# Alpha_Power_Board_v7.net
KiCad netlist of a schematic drawn in EAGLE
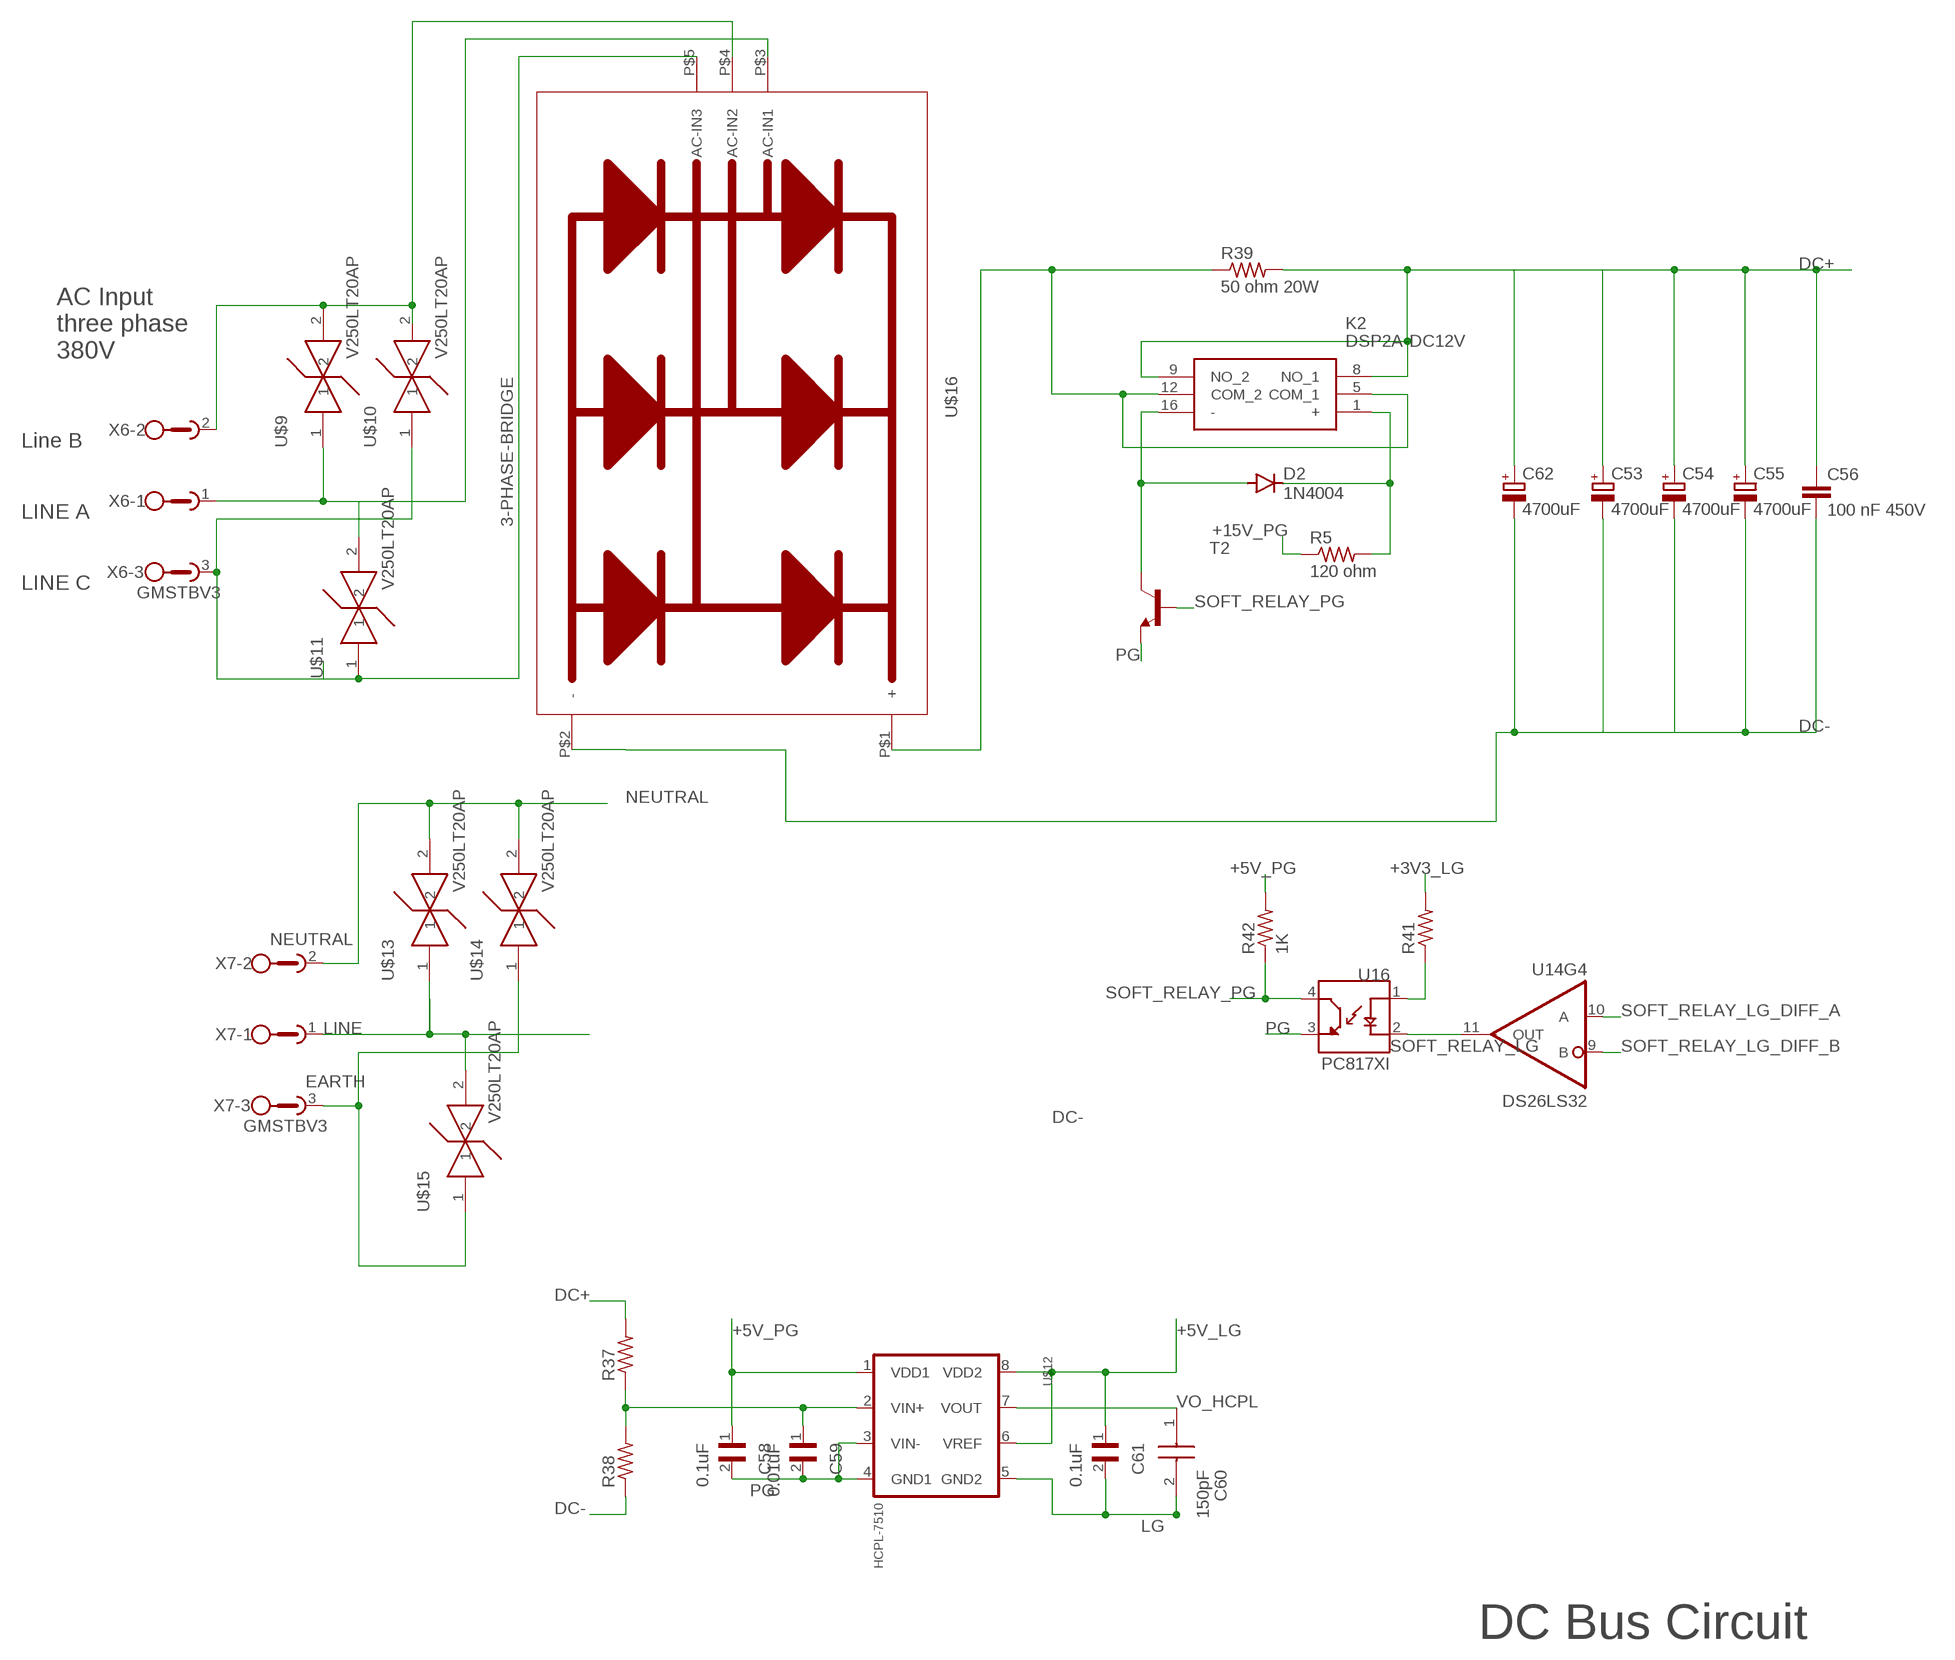
[diagram p0: schematic, sheet 1]
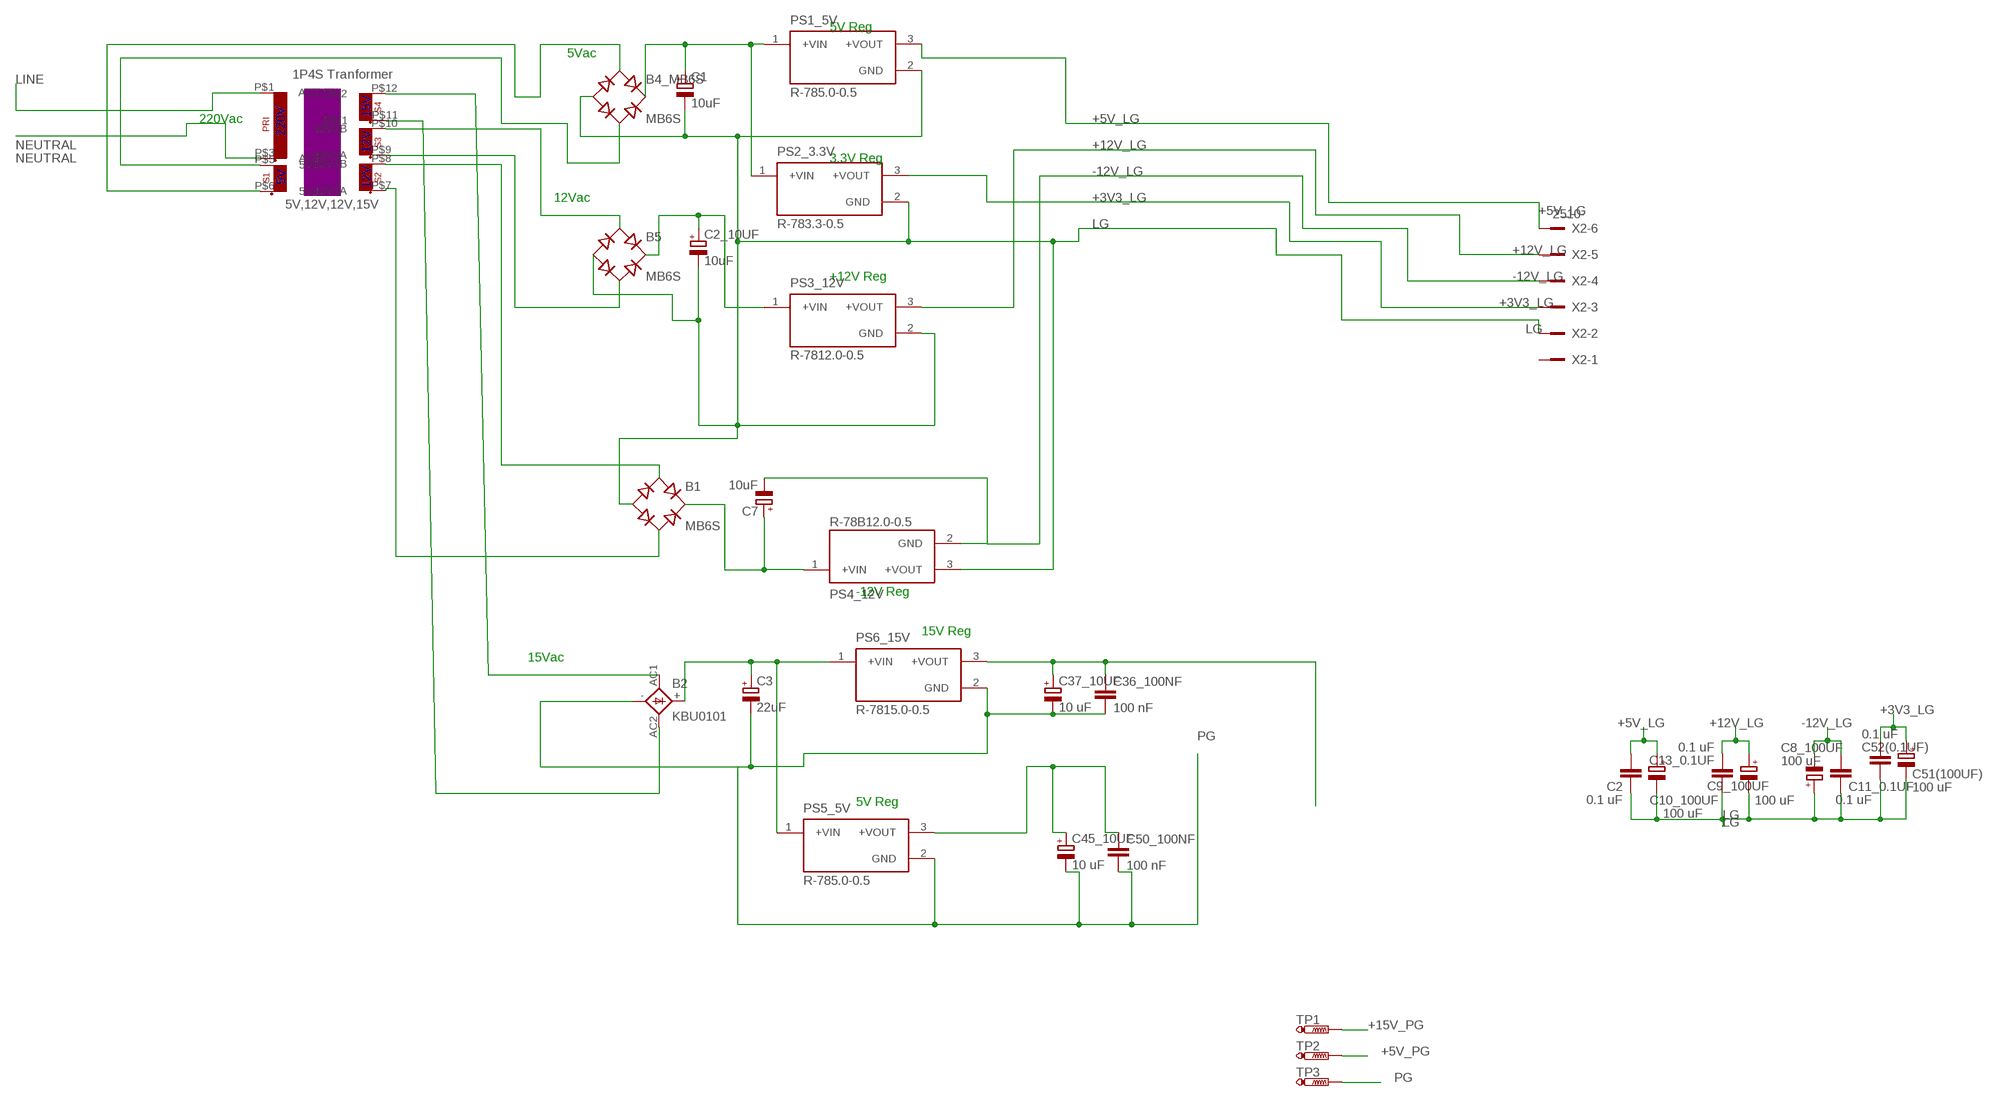
[diagram p1: schematic, sheet 2]
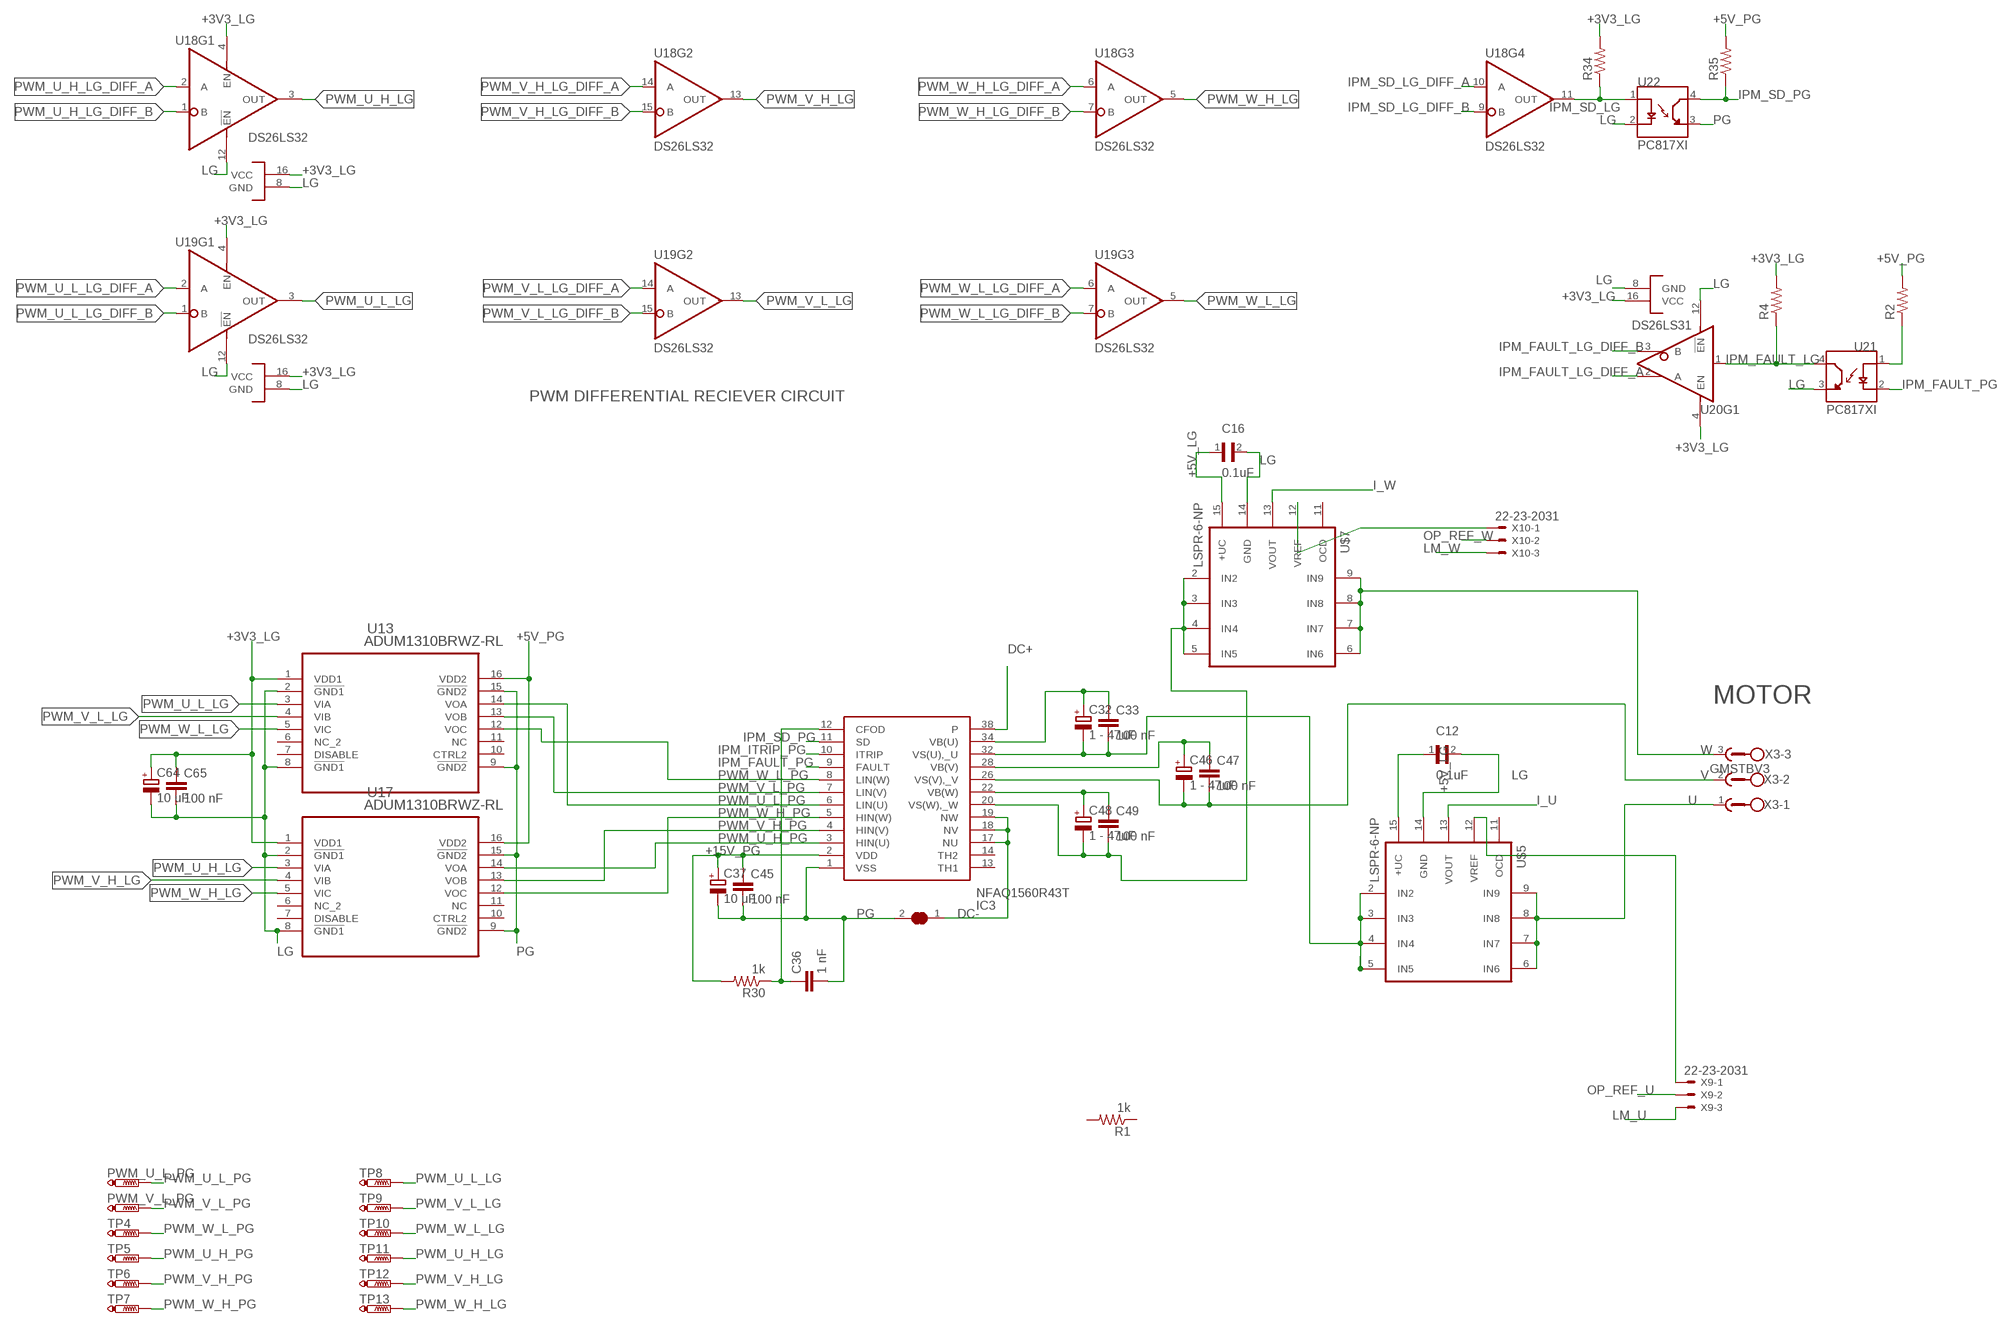
[diagram p2: schematic, sheet 3]
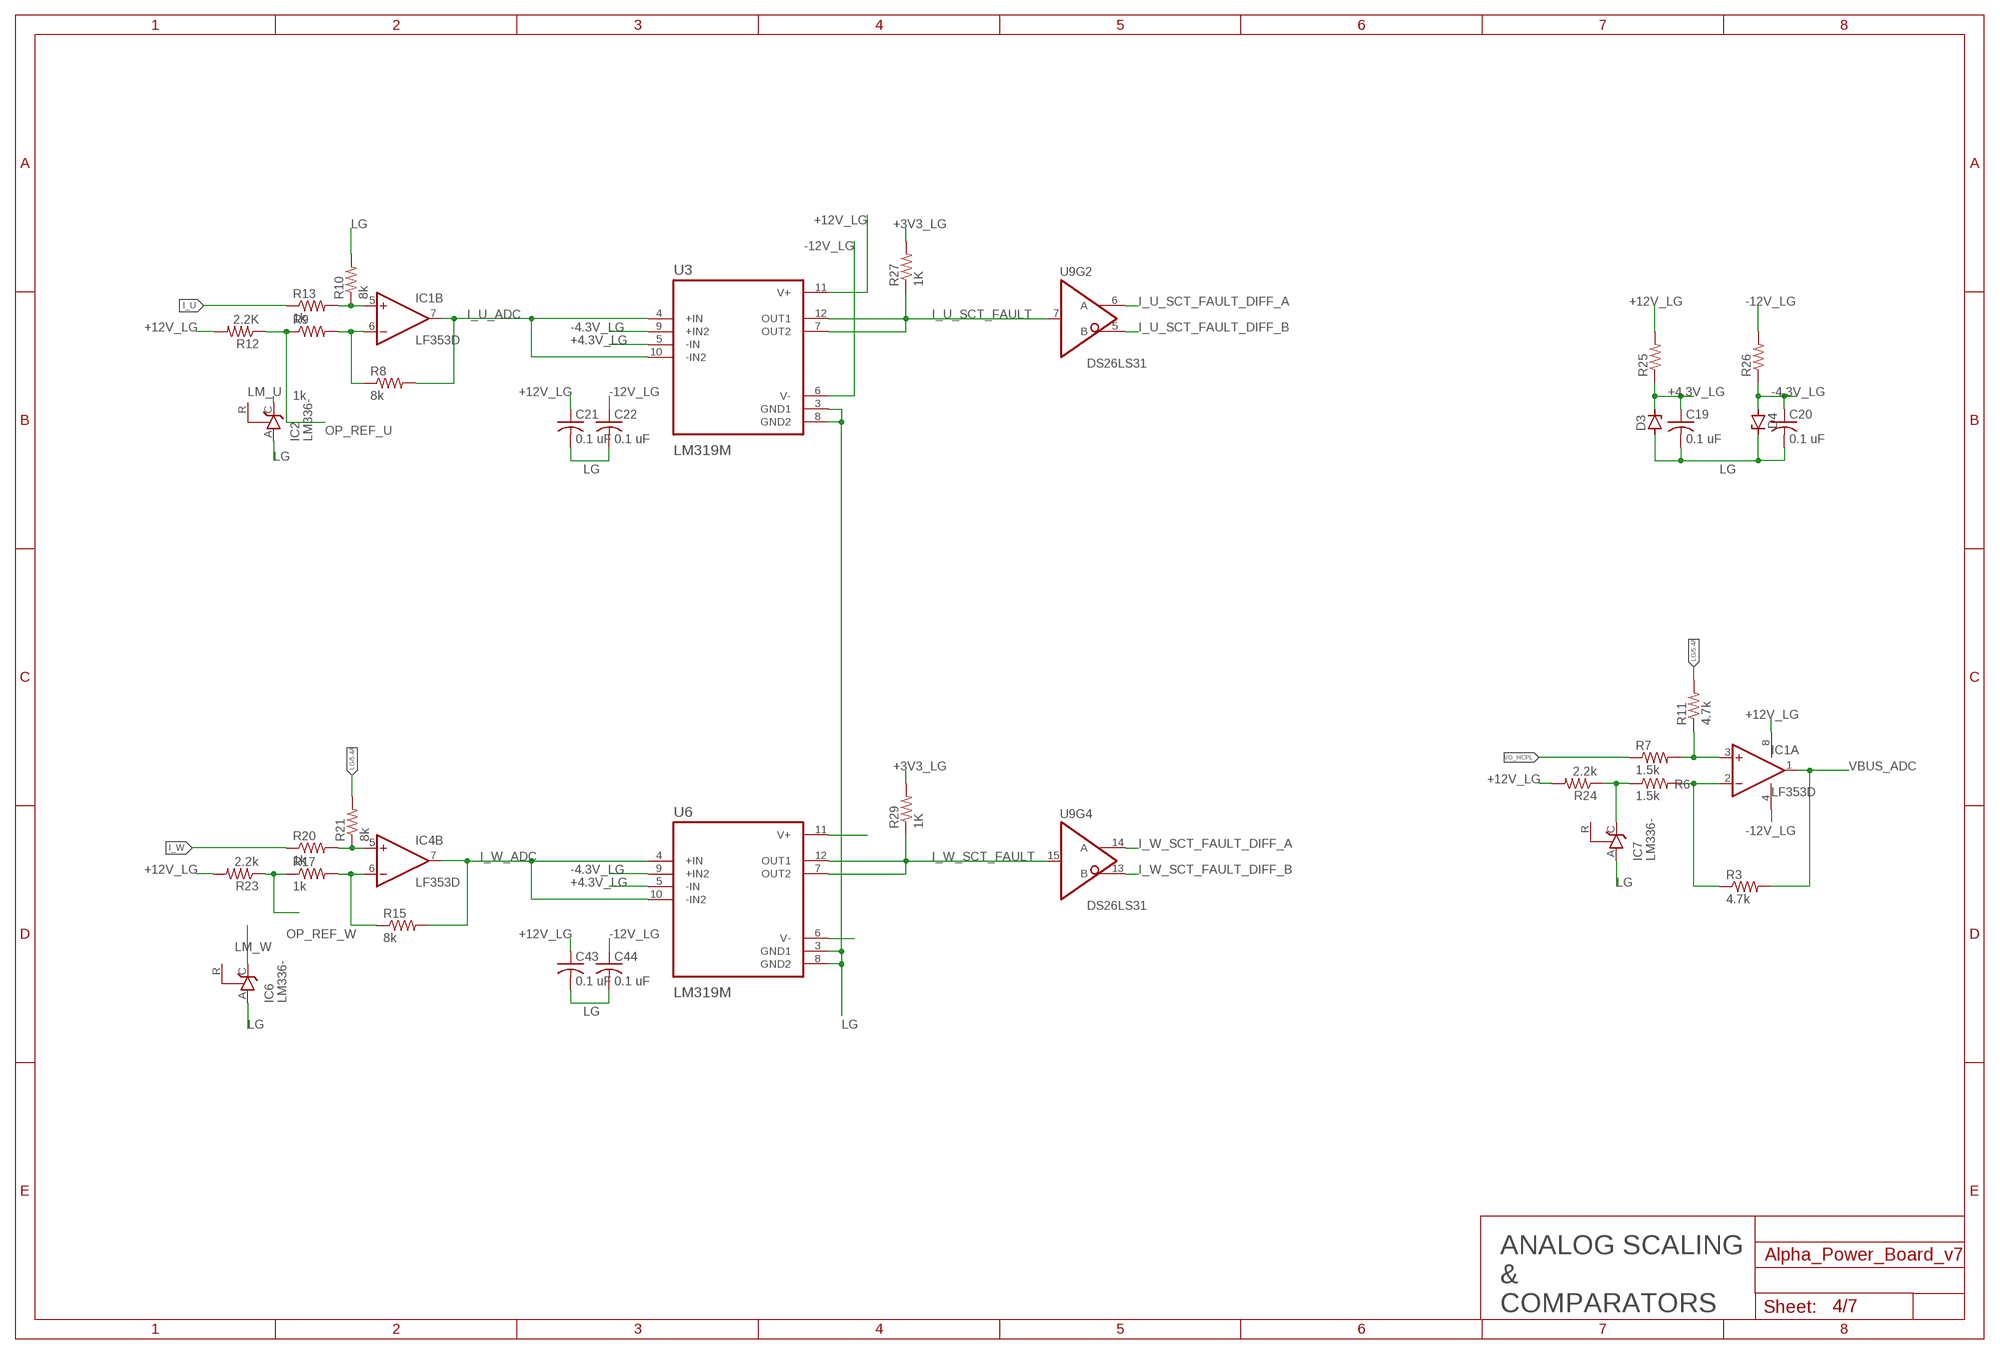
[diagram p3: schematic, sheet 4]
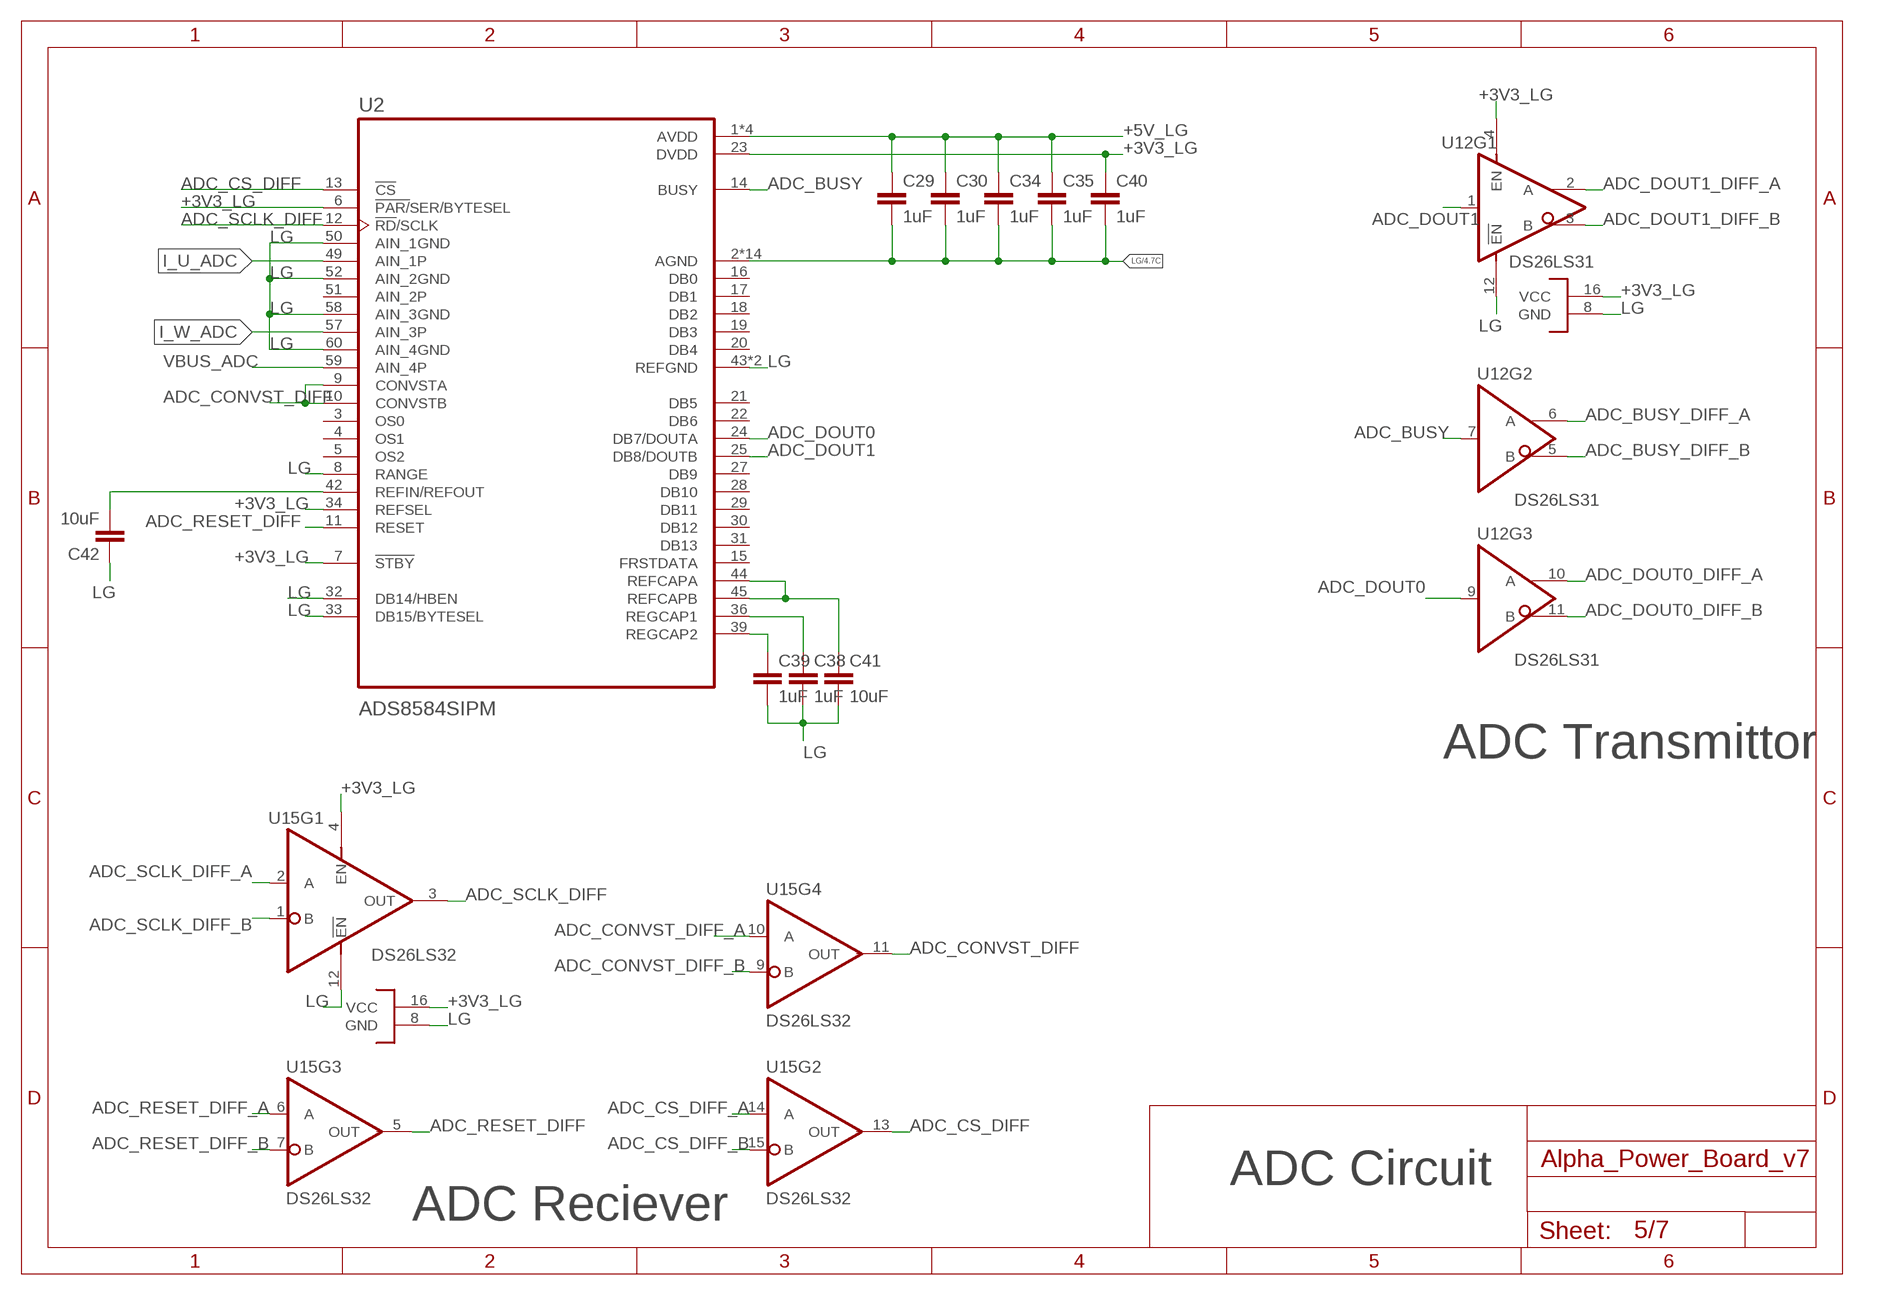
[diagram p4: schematic, sheet 5]
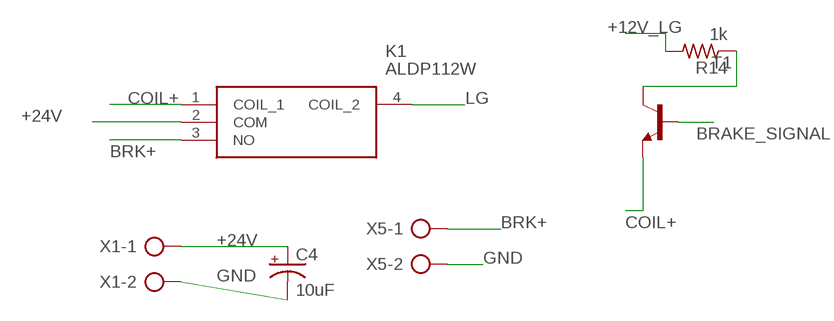
[diagram p5: schematic, sheet 6]
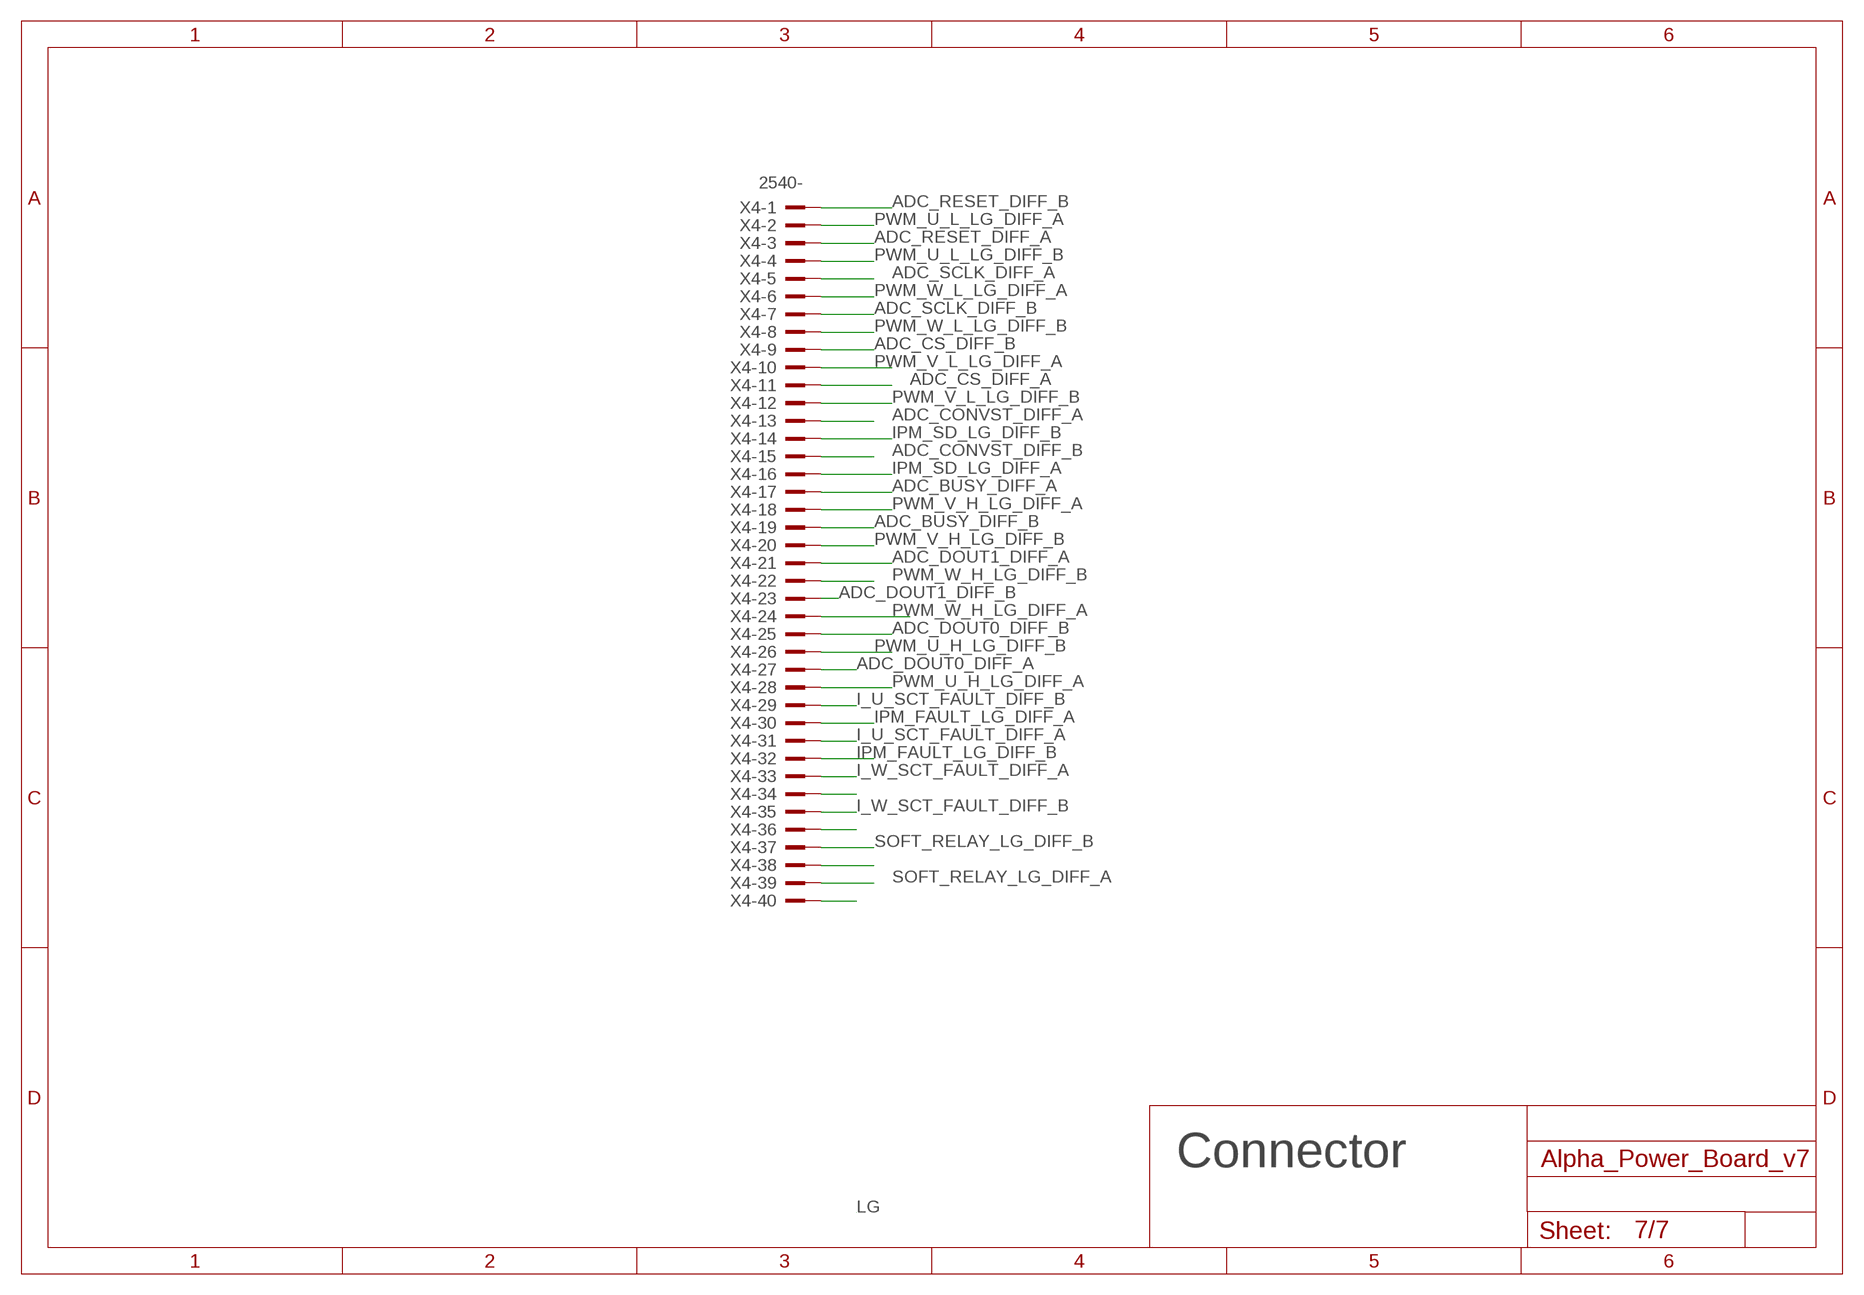
[diagram p6: schematic, sheet 7]

(export (version "E")
  (design (tool "Eeschema 10.0.6"))
  (components
    (comp (ref "B1")
      (value "MB6S")
      (footprint "eagle-import:SOIC-4")
      (libsource (lib "eagle-import") (part "MBS6"))
    )
    (comp (ref "B2")
      (value "KBU0101")
      (footprint "eagle-import:KBU")
      (libsource (lib "eagle-import") (part "KBU"))
    )
    (comp (ref "B4_MB6S")
      (value "MB6S")
      (footprint "eagle-import:SOIC-4")
      (libsource (lib "eagle-import") (part "MBS6"))
    )
    (comp (ref "B5")
      (value "MB6S")
      (footprint "eagle-import:SOIC-4")
      (libsource (lib "eagle-import") (part "MBS6"))
    )
    (comp (ref "C1")
      (value "10uF")
      (footprint "eagle-import:E2,5-6E")
      (libsource (lib "eagle-import") (part "rcl_334_CPOL-EUE2,5-6E"))
    )
    (comp (ref "C2")
      (value "0.1 uF")
      (footprint "eagle-import:C1206")
      (libsource (lib "eagle-import") (part "C-EUC1206"))
    )
    (comp (ref "C2_10UF")
      (value "10uF")
      (footprint "eagle-import:E2,5-6E")
      (libsource (lib "eagle-import") (part "rcl_334_CPOL-EUE2,5-6E"))
    )
    (comp (ref "C3")
      (value "22uF")
      (footprint "eagle-import:E2,5-6E")
      (libsource (lib "eagle-import") (part "rcl_334_CPOL-EUE2,5-6E"))
    )
    (comp (ref "C7")
      (value "10uF")
      (footprint "eagle-import:E2,5-6E")
      (libsource (lib "eagle-import") (part "rcl_334_CPOL-EUE2,5-6E"))
    )
    (comp (ref "C8_100UF")
      (value "100 uF")
      (footprint "eagle-import:153CLV-0605")
      (libsource (lib "eagle-import") (part "CPOL-EU153CLV-0605"))
    )
    (comp (ref "C9_100UF")
      (value "100 uF")
      (footprint "eagle-import:153CLV-0605")
      (libsource (lib "eagle-import") (part "CPOL-EU153CLV-0605"))
    )
    (comp (ref "C10_100UF")
      (value "100 uF")
      (footprint "eagle-import:153CLV-0605")
      (libsource (lib "eagle-import") (part "CPOL-EU153CLV-0605"))
    )
    (comp (ref "C11_0.1UF")
      (value "0.1 uF")
      (footprint "eagle-import:C1206")
      (libsource (lib "eagle-import") (part "rcl_334_C-EUC1206"))
    )
    (comp (ref "C13_0.1UF")
      (value "0.1 uF")
      (footprint "eagle-import:C1206")
      (libsource (lib "eagle-import") (part "C-EUC1206"))
    )
    (comp (ref "C36_100NF")
      (value "100 nF")
      (footprint "eagle-import:C025-025X050")
      (libsource (lib "eagle-import") (part "C-EU025-025X050"))
    )
    (comp (ref "C37_10UF")
      (value "10 uF")
      (footprint "eagle-import:TT2D5")
      (libsource (lib "eagle-import") (part "CPOL-EUTT2D5"))
    )
    (comp (ref "C45_10UF")
      (value "10 uF")
      (footprint "eagle-import:TT2D5")
      (libsource (lib "eagle-import") (part "CPOL-EUTT2D5"))
    )
    (comp (ref "C50_100NF")
      (value "100 nF")
      (footprint "eagle-import:C025-025X050")
      (libsource (lib "eagle-import") (part "C-EU025-025X050"))
    )
    (comp (ref "C51(100UF)")
      (value "100 uF")
      (footprint "eagle-import:153CLV-0605")
      (libsource (lib "eagle-import") (part "CPOL-EU153CLV-0605"))
    )
    (comp (ref "C52(0.1UF)")
      (value "0.1 uF")
      (footprint "eagle-import:C1206")
      (libsource (lib "eagle-import") (part "C-EUC1206"))
    )
    (comp (ref "PS1_5V")
      (value "R-785.0-0.5")
      (footprint "eagle-import:CONV_R-78E5.0-0.5")
      (fields (field (name "MF") "Recom Power") (field (name "MP") "R-78E5.0-0.5"))
      (libsource (lib "eagle-import") (part "R-78E5.0-0.5"))
    )
    (comp (ref "PS2_3.3V")
      (value "R-783.3-0.5")
      (footprint "eagle-import:CONV_R-78E5.0-0.5")
      (fields (field (name "MF") "Recom Power") (field (name "MP") "R-78E5.0-0.5"))
      (libsource (lib "eagle-import") (part "R-78E5.0-0.5"))
    )
    (comp (ref "PS3_12V")
      (value "R-7812.0-0.5")
      (footprint "eagle-import:CONV_R-78E5.0-0.5")
      (fields (field (name "MF") "Recom Power") (field (name "MP") "R-78E5.0-0.5"))
      (libsource (lib "eagle-import") (part "R-78E5.0-0.5"))
    )
    (comp (ref "PS4_12V")
      (value "R-78B12.0-0.5")
      (footprint "eagle-import:CONV_R-78E5.0-0.5")
      (fields (field (name "MF") "Recom Power") (field (name "MP") "R-78E5.0-0.5"))
      (libsource (lib "eagle-import") (part "R-78E5.0-0.5"))
    )
    (comp (ref "PS5_5V")
      (value "R-785.0-0.5")
      (footprint "eagle-import:CONV_R-78E5.0-0.5")
      (fields (field (name "MF") "Recom Power") (field (name "MP") "R-78E5.0-0.5"))
      (libsource (lib "eagle-import") (part "R-78E5.0-0.5"))
    )
    (comp (ref "PS6_15V")
      (value "R-7815.0-0.5")
      (footprint "eagle-import:CONV_R-78E5.0-0.5")
      (fields (field (name "MF") "Recom Power") (field (name "MP") "R-78E5.0-0.5"))
      (libsource (lib "eagle-import") (part "R-78E5.0-0.5"))
    )
    (comp (ref "TP1")
      (value "PTR1PAD1-13")
      (footprint "eagle-import:P1-13")
      (libsource (lib "eagle-import") (part "PTR1PAD1-13"))
    )
    (comp (ref "TP2")
      (value "PTR1PAD1-13")
      (footprint "eagle-import:P1-13")
      (libsource (lib "eagle-import") (part "PTR1PAD1-13"))
    )
    (comp (ref "TP3")
      (value "PTR1PAD1-13")
      (footprint "eagle-import:P1-13")
      (libsource (lib "eagle-import") (part "PTR1PAD1-13"))
    )
    (comp (ref "U$1")
      (value "TRANSFORMERTHROUGH-HOLE")
      (footprint "eagle-import:T1P2S")
      (libsource (lib "eagle-import") (part "TRANSFORMERTHROUGH-HOLE"))
    )
    (comp (ref "X2")
      (value "2510-")
      (footprint "eagle-import:PAK100_2500-10")
      (fields (field (name "MF") "3M") (field (name "MPN") "2510-6002UB"))
      (libsource (lib "eagle-import") (part "2510-"))
    )
    (comp (ref "C53")
      (value "4700uF")
      (footprint "eagle-import:EB35D")
      (libsource (lib "eagle-import") (part "resistor_CPOL-EUE10-35"))
    )
    (comp (ref "C54")
      (value "4700uF")
      (footprint "eagle-import:EB35D")
      (libsource (lib "eagle-import") (part "resistor_CPOL-EUE10-35"))
    )
    (comp (ref "C55")
      (value "4700uF")
      (footprint "eagle-import:EB35D")
      (libsource (lib "eagle-import") (part "resistor_CPOL-EUE10-35"))
    )
    (comp (ref "C56")
      (value "100 nF 450V")
      (footprint "eagle-import:C102-064X133")
      (libsource (lib "eagle-import") (part "C-EU102-064X133"))
    )
    (comp (ref "C58")
      (value "0.1uF")
      (footprint "eagle-import:CAPC3316X140N")
      (fields (field (name "MF") "KEMET") (field (name "MP") "C1206X104J3REC7210"))
      (libsource (lib "eagle-import") (part "C1206X104J3REC7210"))
    )
    (comp (ref "C59")
      (value "0.01uF")
      (footprint "eagle-import:CAPC3316X140N")
      (fields (field (name "MF") "KEMET") (field (name "MP") "C1206X104J3REC7210"))
      (libsource (lib "eagle-import") (part "C1206X104J3REC7210"))
    )
    (comp (ref "C60")
      (value "150pF")
      (footprint "eagle-import:CAP150PF")
      (fields
        (field (name "MANUFACTURER_PART_NUMBER") "GCM31A7U2J151JX01D")
        (field (name "MOUSER_PART_NUMBER") "81-GCM31A7U2J151JX1D")
      )
      (libsource (lib "eagle-import") (part "CAP150PF"))
    )
    (comp (ref "C61")
      (value "0.1uF")
      (footprint "eagle-import:CAPC3316X140N")
      (fields (field (name "MF") "KEMET") (field (name "MP") "C1206X104J3REC7210"))
      (libsource (lib "eagle-import") (part "C1206X104J3REC7210"))
    )
    (comp (ref "C62")
      (value "4700uF")
      (footprint "eagle-import:EB35D")
      (libsource (lib "eagle-import") (part "resistor_CPOL-EUE10-35"))
    )
    (comp (ref "D2")
      (value "1N4004")
      (footprint "eagle-import:DO41-10")
      (libsource (lib "eagle-import") (part "1N4004"))
    )
    (comp (ref "K2")
      (value "DSP2A-DC12V")
      (footprint "eagle-import:DSP2ADC12V")
      (fields (field (name "MOUSER_PART_NUMBER") "769-DSP2A-DC12V"))
      (libsource (lib "eagle-import") (part "DSP2A-DC12V"))
    )
    (comp (ref "R5")
      (value "120 ohm")
      (footprint "eagle-import:0207_15")
      (libsource (lib "eagle-import") (part "rcl_334_R-US_0207/15"))
    )
    (comp (ref "R37")
      (value "R-US_0309/12")
      (footprint "eagle-import:0309_12")
      (libsource (lib "eagle-import") (part "rcl_334_R-US_0309/12"))
    )
    (comp (ref "R38")
      (value "R-US_0309/12")
      (footprint "eagle-import:0309_12")
      (libsource (lib "eagle-import") (part "rcl_334_R-US_0309/12"))
    )
    (comp (ref "R39")
      (value "50 ohm 20W")
      (footprint "eagle-import:B20J50RE")
      (libsource (lib "eagle-import") (part "B20J50RE"))
    )
    (comp (ref "R41")
      (value "R-US_R1206")
      (footprint "eagle-import:R1206")
      (libsource (lib "eagle-import") (part "rcl@2_R-US_R1206"))
    )
    (comp (ref "R42")
      (value "1K")
      (footprint "eagle-import:R1206")
      (libsource (lib "eagle-import") (part "rcl@2_R-US_R1206"))
    )
    (comp (ref "T2")
      (value "MMBT2222ALT1-NPN-SOT23-BEC")
      (footprint "eagle-import:SOT23-BEC")
      (libsource (lib "eagle-import") (part "-NPN-SOT23-BECMMBT2222ALT1"))
    )
    (comp (ref "U$9")
      (value "V250LT20AP")
      (footprint "eagle-import:V250LT20AP")
      (fields (field (name "MF") "Littelfuse Inc.") (field (name "MP") "V18ZA2P"))
      (libsource (lib "eagle-import") (part "V250LT20AP"))
    )
    (comp (ref "U$10")
      (value "V250LT20AP")
      (footprint "eagle-import:V250LT20AP")
      (fields (field (name "MF") "Littelfuse Inc.") (field (name "MP") "V18ZA2P"))
      (libsource (lib "eagle-import") (part "V250LT20AP"))
    )
    (comp (ref "U$11")
      (value "V250LT20AP")
      (footprint "eagle-import:V250LT20AP")
      (fields (field (name "MF") "Littelfuse Inc.") (field (name "MP") "V18ZA2P"))
      (libsource (lib "eagle-import") (part "V250LT20AP"))
    )
    (comp (ref "U$12")
      (value "HCPL-7510")
      (footprint "eagle-import:HCPL-7510")
      (libsource (lib "eagle-import") (part "HCPL-7510U"))
    )
    (comp (ref "U$13")
      (value "V250LT20AP")
      (footprint "eagle-import:V250LT20AP")
      (fields (field (name "MF") "Littelfuse Inc.") (field (name "MP") "V18ZA2P"))
      (libsource (lib "eagle-import") (part "V250LT20AP"))
    )
    (comp (ref "U$14")
      (value "V250LT20AP")
      (footprint "eagle-import:V250LT20AP")
      (fields (field (name "MF") "Littelfuse Inc.") (field (name "MP") "V18ZA2P"))
      (libsource (lib "eagle-import") (part "V250LT20AP"))
    )
    (comp (ref "U$15")
      (value "V250LT20AP")
      (footprint "eagle-import:V250LT20AP")
      (fields (field (name "MF") "Littelfuse Inc.") (field (name "MP") "V18ZA2P"))
      (libsource (lib "eagle-import") (part "V250LT20AP"))
    )
    (comp (ref "U$16")
      (value "3-PHASE-BRIDGE")
      (footprint "eagle-import:3-PHASE-BRIDGE")
      (libsource (lib "eagle-import") (part "3-PHASE-BRIDGE"))
    )
    (comp (ref "U14")
      (value "DS26LS32")
      (footprint "eagle-import:SOIC_16")
      (libsource (lib "eagle-import") (part "DS26LS32"))
    )
    (comp (ref "U16")
      (value "PC817XI")
      (footprint "eagle-import:SOIC254P975X460-4N")
      (fields (field (name "MF") "Sharp Microelectronics"))
      (libsource (lib "eagle-import") (part "PC817XI"))
    )
    (comp (ref "X6")
      (value "GMSTBV3")
      (footprint "eagle-import:GMSTBV3")
      (fields (field (name "MPN") "GMSTBVA2,5/3-G-7,62"))
      (libsource (lib "eagle-import") (part "con-phoenix-762_177_GMSTBV3"))
    )
    (comp (ref "X7")
      (value "GMSTBV3")
      (footprint "eagle-import:GMSTBV3")
      (fields (field (name "MPN") "GMSTBVA2,5/3-G-7,62"))
      (libsource (lib "eagle-import") (part "GMSTBV3"))
    )
    (comp (ref "C4")
      (value "10uF")
      (footprint "eagle-import:E2,5-6E")
      (libsource (lib "eagle-import") (part "CPOL-USE2,5-6E"))
    )
    (comp (ref "K1")
      (value "ALDP112W")
      (footprint "eagle-import:ALDP112W")
      (fields (field (name "MOUSER_PART_NUMBER") "769-ALDP112W"))
      (libsource (lib "eagle-import") (part "ALDP112W"))
    )
    (comp (ref "R14")
      (value "1k")
      (footprint "eagle-import:0204V")
      (libsource (lib "eagle-import") (part "rcl_R-US_0204/2V"))
    )
    (comp (ref "T1")
      (value "MMBT2222ALT1-NPN-SOT23-BEC")
      (footprint "eagle-import:SOT23-BEC")
      (libsource (lib "eagle-import") (part "-NPN-SOT23-BECMMBT2222ALT1"))
    )
    (comp (ref "X1")
      (value "AK500/2-H")
      (footprint "eagle-import:AK500_2-H")
      (libsource (lib "eagle-import") (part "AK500/2-H"))
    )
    (comp (ref "X5")
      (value "AK500/2-H")
      (footprint "eagle-import:AK500_2-H")
      (libsource (lib "eagle-import") (part "AK500/2-H"))
    )
    (comp (ref "C29")
      (value "1uF")
      (footprint "eagle-import:C0603")
      (libsource (lib "eagle-import") (part "rcl@1_C-EUC0603"))
    )
    (comp (ref "C30")
      (value "1uF")
      (footprint "eagle-import:C0603")
      (libsource (lib "eagle-import") (part "rcl@1_C-EUC0603"))
    )
    (comp (ref "C34")
      (value "1uF")
      (footprint "eagle-import:C0603")
      (libsource (lib "eagle-import") (part "rcl@1_C-EUC0603"))
    )
    (comp (ref "C35")
      (value "1uF")
      (footprint "eagle-import:C0603")
      (libsource (lib "eagle-import") (part "rcl@1_C-EUC0603"))
    )
    (comp (ref "C38")
      (value "1uF")
      (footprint "eagle-import:C0603")
      (libsource (lib "eagle-import") (part "rcl@1_C-EUC0603"))
    )
    (comp (ref "C39")
      (value "1uF")
      (footprint "eagle-import:C0603")
      (libsource (lib "eagle-import") (part "rcl@1_C-EUC0603"))
    )
    (comp (ref "C40")
      (value "1uF")
      (footprint "eagle-import:C0603")
      (libsource (lib "eagle-import") (part "rcl@1_C-EUC0603"))
    )
    (comp (ref "C41")
      (value "10uF")
      (footprint "eagle-import:C0603")
      (libsource (lib "eagle-import") (part "rcl@1_C-EUC0603"))
    )
    (comp (ref "C42")
      (value "10uF")
      (footprint "eagle-import:C0603")
      (libsource (lib "eagle-import") (part "rcl@1_C-EUC0603"))
    )
    (comp (ref "U2")
      (value "ADS8584SIPM")
      (footprint "eagle-import:QFP50P1200X1200X160-64N")
      (fields (field (name "MF") "Texas Instruments"))
      (libsource (lib "eagle-import") (part "ADS8584SIPM"))
    )
    (comp (ref "U12")
      (value "DS26LS31")
      (footprint "eagle-import:SOIC_16")
      (libsource (lib "eagle-import") (part "DS26LS31"))
    )
    (comp (ref "U15")
      (value "DS26LS32")
      (footprint "eagle-import:SOIC_16")
      (libsource (lib "eagle-import") (part "DS26LS32"))
    )
    (comp (ref "C19")
      (value "0.1 uF")
      (footprint "eagle-import:C1206")
      (libsource (lib "eagle-import") (part "C-USC1206"))
    )
    (comp (ref "C20")
      (value "0.1 uF")
      (footprint "eagle-import:C1206")
      (libsource (lib "eagle-import") (part "C-USC1206"))
    )
    (comp (ref "C21")
      (value "0.1 uF")
      (footprint "eagle-import:C1206")
      (libsource (lib "eagle-import") (part "C-USC1206"))
    )
    (comp (ref "C22")
      (value "0.1 uF")
      (footprint "eagle-import:C1206")
      (libsource (lib "eagle-import") (part "C-USC1206"))
    )
    (comp (ref "C43")
      (value "0.1 uF")
      (footprint "eagle-import:C1206")
      (libsource (lib "eagle-import") (part "C-USC1206"))
    )
    (comp (ref "C44")
      (value "0.1 uF")
      (footprint "eagle-import:C1206")
      (libsource (lib "eagle-import") (part "C-USC1206"))
    )
    (comp (ref "D3")
      (value "ZENER-DIODETO236")
      (footprint "eagle-import:TO236")
      (libsource (lib "eagle-import") (part "ZENER-DIODETO236"))
    )
    (comp (ref "D4")
      (value "ZENER-DIODETO236")
      (footprint "eagle-import:TO236")
      (fields (field (name "SPICEPREFIX") "D"))
      (libsource (lib "eagle-import") (part "ZENER-DIODETO236"))
    )
    (comp (ref "IC1")
      (value "LF353D")
      (footprint "eagle-import:SO08")
      (fields (field (name "MF") "ON Semiconductor") (field (name "MP") "LF353"))
      (libsource (lib "eagle-import") (part "LF353D"))
    )
    (comp (ref "IC2")
      (value "LM336-")
      (footprint "eagle-import:TO92A_VREF")
      (libsource (lib "eagle-import") (part "LM336-"))
    )
    (comp (ref "IC4")
      (value "LF353D")
      (footprint "eagle-import:SO08")
      (fields (field (name "MF") "ON Semiconductor") (field (name "MP") "LF353"))
      (libsource (lib "eagle-import") (part "LF353D"))
    )
    (comp (ref "IC6")
      (value "LM336-")
      (footprint "eagle-import:TO92A_VREF")
      (libsource (lib "eagle-import") (part "LM336-"))
    )
    (comp (ref "IC7")
      (value "LM336-")
      (footprint "eagle-import:TO92A_VREF")
      (libsource (lib "eagle-import") (part "LM336-"))
    )
    (comp (ref "R3")
      (value "4.7k")
      (footprint "eagle-import:M1206")
      (libsource (lib "eagle-import") (part "R-US_M1206"))
    )
    (comp (ref "R6")
      (value "1.5k")
      (footprint "eagle-import:M1206")
      (libsource (lib "eagle-import") (part "R-US_M1206"))
    )
    (comp (ref "R7")
      (value "1.5k")
      (footprint "eagle-import:R1206")
      (libsource (lib "eagle-import") (part "R-US_R1206"))
    )
    (comp (ref "R8")
      (value "8k")
      (footprint "eagle-import:M1206")
      (libsource (lib "eagle-import") (part "R-US_M1206"))
    )
    (comp (ref "R9")
      (value "1k")
      (footprint "eagle-import:M1206")
      (libsource (lib "eagle-import") (part "R-US_M1206"))
    )
    (comp (ref "R10")
      (value "8k")
      (footprint "eagle-import:M1206")
      (libsource (lib "eagle-import") (part "R-US_M1206"))
    )
    (comp (ref "R11")
      (value "4.7k")
      (footprint "eagle-import:M1206")
      (libsource (lib "eagle-import") (part "R-US_M1206"))
    )
    (comp (ref "R12")
      (value "2.2K")
      (footprint "eagle-import:M1206")
      (libsource (lib "eagle-import") (part "R-US_M1206"))
    )
    (comp (ref "R13")
      (value "1k")
      (footprint "eagle-import:M1206")
      (libsource (lib "eagle-import") (part "R-US_M1206"))
    )
    (comp (ref "R15")
      (value "8k")
      (footprint "eagle-import:M1206")
      (libsource (lib "eagle-import") (part "R-US_M1206"))
    )
    (comp (ref "R17")
      (value "1k")
      (footprint "eagle-import:M1206")
      (libsource (lib "eagle-import") (part "R-US_M1206"))
    )
    (comp (ref "R20")
      (value "1k")
      (footprint "eagle-import:M1206")
      (libsource (lib "eagle-import") (part "R-US_M1206"))
    )
    (comp (ref "R21")
      (value "8k")
      (footprint "eagle-import:M1206")
      (libsource (lib "eagle-import") (part "R-US_M1206"))
    )
    (comp (ref "R23")
      (value "2.2k")
      (footprint "eagle-import:M1206")
      (libsource (lib "eagle-import") (part "R-US_M1206"))
    )
    (comp (ref "R24")
      (value "2.2k")
      (footprint "eagle-import:M1206")
      (libsource (lib "eagle-import") (part "R-US_M1206"))
    )
    (comp (ref "R25")
      (value "R-US_M1206")
      (footprint "eagle-import:M1206")
      (libsource (lib "eagle-import") (part "rcl@2_R-US_M1206"))
    )
    (comp (ref "R26")
      (value "R-US_M1206")
      (footprint "eagle-import:M1206")
      (libsource (lib "eagle-import") (part "rcl@2_R-US_M1206"))
    )
    (comp (ref "R27")
      (value "1K")
      (footprint "eagle-import:R1206")
      (libsource (lib "eagle-import") (part "rcl@2_R-US_R1206"))
    )
    (comp (ref "R29")
      (value "1K")
      (footprint "eagle-import:R1206")
      (libsource (lib "eagle-import") (part "rcl@2_R-US_R1206"))
    )
    (comp (ref "U3")
      (value "LM319M")
      (footprint "eagle-import:SOIC127P600X175-14N")
      (fields (field (name "MF") "Texas Instruments"))
      (libsource (lib "eagle-import") (part "LM319M"))
    )
    (comp (ref "U6")
      (value "LM319M")
      (footprint "eagle-import:SOIC127P600X175-14N")
      (fields (field (name "MF") "Texas Instruments"))
      (libsource (lib "eagle-import") (part "LM319M"))
    )
    (comp (ref "U9")
      (value "DS26LS31")
      (footprint "eagle-import:SOIC_16")
      (libsource (lib "eagle-import") (part "DS26LS31"))
    )
    (comp (ref "C12")
      (value "0.1uF")
      (footprint "eagle-import:CAPC3316X140N")
      (fields (field (name "MF") "KEMET") (field (name "MP") "C1206X104J3REC7210"))
      (libsource (lib "eagle-import") (part "C1206X104J3REC7210"))
    )
    (comp (ref "C16")
      (value "0.1uF")
      (footprint "eagle-import:CAPC3316X140N")
      (fields (field (name "MF") "KEMET") (field (name "MP") "C1206X104J3REC7210"))
      (libsource (lib "eagle-import") (part "C1206X104J3REC7210"))
    )
    (comp (ref "C32")
      (value "1 - 47uF")
      (footprint "eagle-import:E3,5-8")
      (libsource (lib "eagle-import") (part "CPOL-EUE3.5-8"))
    )
    (comp (ref "C33")
      (value "100 nF")
      (footprint "eagle-import:C025-030X050")
      (libsource (lib "eagle-import") (part "C-EU025-030X050"))
    )
    (comp (ref "C36")
      (value "1 nF")
      (footprint "eagle-import:C025-025X050")
      (libsource (lib "eagle-import") (part "C-EU025-025X050"))
    )
    (comp (ref "C37")
      (value "10 uF")
      (footprint "eagle-import:TT2D5")
      (libsource (lib "eagle-import") (part "CPOL-EUTT2D5"))
    )
    (comp (ref "C45")
      (value "100 nF")
      (footprint "eagle-import:C025-025X050")
      (libsource (lib "eagle-import") (part "C-EU025-025X050"))
    )
    (comp (ref "C46")
      (value "1 - 47uF")
      (footprint "eagle-import:E3,5-8")
      (libsource (lib "eagle-import") (part "CPOL-EUE3.5-8"))
    )
    (comp (ref "C47")
      (value "100 nF")
      (footprint "eagle-import:C025-030X050")
      (libsource (lib "eagle-import") (part "C-EU025-030X050"))
    )
    (comp (ref "C48")
      (value "1 - 47uF")
      (footprint "eagle-import:E3,5-8")
      (libsource (lib "eagle-import") (part "CPOL-EUE3.5-8"))
    )
    (comp (ref "C49")
      (value "100 nF")
      (footprint "eagle-import:C025-030X050")
      (libsource (lib "eagle-import") (part "C-EU025-030X050"))
    )
    (comp (ref "C64")
      (value "10 uF")
      (footprint "eagle-import:SMC_P")
      (libsource (lib "eagle-import") (part "CPOL-EUSMCP"))
    )
    (comp (ref "C65")
      (value "100 nF")
      (footprint "eagle-import:C1206")
      (libsource (lib "eagle-import") (part "C-EUC1206"))
    )
    (comp (ref "IC3")
      (value "NFAQ1560R43T")
      (footprint "eagle-import:NFAQ1560R43T")
      (libsource (lib "eagle-import") (part "NFAQ1560R43T"))
    )
    (comp (ref "PWM_U_L_PG")
      (value "PTR1PAD1-13")
      (footprint "eagle-import:P1-13")
      (libsource (lib "eagle-import") (part "PTR1PAD1-13"))
    )
    (comp (ref "PWM_V_L_PG")
      (value "PTR1PAD1-13")
      (footprint "eagle-import:P1-13")
      (libsource (lib "eagle-import") (part "PTR1PAD1-13"))
    )
    (comp (ref "R1")
      (value "1k")
      (footprint "eagle-import:0204V")
      (libsource (lib "eagle-import") (part "rcl_R-US_0204/2V"))
    )
    (comp (ref "R2")
      (value "R-US_R1206")
      (footprint "eagle-import:R1206")
      (libsource (lib "eagle-import") (part "rcl@2_R-US_R1206"))
    )
    (comp (ref "R4")
      (value "R-US_R1206")
      (footprint "eagle-import:R1206")
      (libsource (lib "eagle-import") (part "rcl@2_R-US_R1206"))
    )
    (comp (ref "R30")
      (value "1k")
      (footprint "eagle-import:0204V")
      (libsource (lib "eagle-import") (part "rcl_R-US_0204/2V"))
    )
    (comp (ref "R34")
      (value "R-US_R0805W")
      (footprint "eagle-import:R0805W")
      (libsource (lib "eagle-import") (part "rcl@2_R-US_R0805W"))
    )
    (comp (ref "R35")
      (value "R-US_R0805")
      (footprint "eagle-import:R0805")
      (libsource (lib "eagle-import") (part "rcl@2_R-US_R0805"))
    )
    (comp (ref "TP4")
      (value "PTR1PAD1-13")
      (footprint "eagle-import:P1-13")
      (libsource (lib "eagle-import") (part "PTR1PAD1-13"))
    )
    (comp (ref "TP5")
      (value "PTR1PAD1-13")
      (footprint "eagle-import:P1-13")
      (libsource (lib "eagle-import") (part "PTR1PAD1-13"))
    )
    (comp (ref "TP6")
      (value "PTR1PAD1-13")
      (footprint "eagle-import:P1-13")
      (libsource (lib "eagle-import") (part "PTR1PAD1-13"))
    )
    (comp (ref "TP7")
      (value "PTR1PAD1-13")
      (footprint "eagle-import:P1-13")
      (libsource (lib "eagle-import") (part "PTR1PAD1-13"))
    )
    (comp (ref "TP8")
      (value "PTR1PAD1-13")
      (footprint "eagle-import:P1-13")
      (libsource (lib "eagle-import") (part "PTR1PAD1-13"))
    )
    (comp (ref "TP9")
      (value "PTR1PAD1-13")
      (footprint "eagle-import:P1-13")
      (libsource (lib "eagle-import") (part "PTR1PAD1-13"))
    )
    (comp (ref "TP10")
      (value "PTR1PAD1-13")
      (footprint "eagle-import:P1-13")
      (libsource (lib "eagle-import") (part "PTR1PAD1-13"))
    )
    (comp (ref "TP11")
      (value "PTR1PAD1-13")
      (footprint "eagle-import:P1-13")
      (libsource (lib "eagle-import") (part "PTR1PAD1-13"))
    )
    (comp (ref "TP12")
      (value "PTR1PAD1-13")
      (footprint "eagle-import:P1-13")
      (libsource (lib "eagle-import") (part "PTR1PAD1-13"))
    )
    (comp (ref "TP13")
      (value "PTR1PAD1-13")
      (footprint "eagle-import:P1-13")
      (libsource (lib "eagle-import") (part "PTR1PAD1-13"))
    )
    (comp (ref "U$2")
      (value "GND_CONNECT")
      (footprint "eagle-import:GND_CONNECT")
      (libsource (lib "eagle-import") (part "GND_CONNECT"))
    )
    (comp (ref "U$5")
      (value "LSPR-6-NP")
      (footprint "eagle-import:LPSR-15-NP")
      (libsource (lib "eagle-import") (part "LSPR-6-NP"))
    )
    (comp (ref "U$7")
      (value "LSPR-6-NP")
      (footprint "eagle-import:LPSR-15-NP")
      (libsource (lib "eagle-import") (part "LSPR-6-NP"))
    )
    (comp (ref "U13")
      (value "ADUM1310BRWZ-RL")
      (footprint "eagle-import:RW_16_ADI")
      (fields (field (name "COPYRIGHT") "Copyright (C) 2018 Accelerated Designs. All rights reserved"))
      (libsource (lib "eagle-import") (part "ADUM1310BRWZ-RL"))
    )
    (comp (ref "U17")
      (value "ADUM1310BRWZ-RL")
      (footprint "eagle-import:RW_16_ADI")
      (fields (field (name "COPYRIGHT") "Copyright (C) 2018 Accelerated Designs. All rights reserved"))
      (libsource (lib "eagle-import") (part "ADUM1310BRWZ-RL"))
    )
    (comp (ref "U18")
      (value "DS26LS32")
      (footprint "eagle-import:SOIC_16")
      (libsource (lib "eagle-import") (part "DS26LS32"))
    )
    (comp (ref "U19")
      (value "DS26LS32")
      (footprint "eagle-import:SOIC_16")
      (libsource (lib "eagle-import") (part "DS26LS32"))
    )
    (comp (ref "U20")
      (value "DS26LS31")
      (footprint "eagle-import:SOIC_16")
      (libsource (lib "eagle-import") (part "DS26LS31"))
    )
    (comp (ref "U21")
      (value "PC817XI")
      (footprint "eagle-import:SOIC254P975X460-4N")
      (fields (field (name "MF") "Sharp Microelectronics"))
      (libsource (lib "eagle-import") (part "PC817XI"))
    )
    (comp (ref "U22")
      (value "PC817XI")
      (footprint "eagle-import:SOIC254P975X460-4N")
      (fields (field (name "MF") "Sharp Microelectronics"))
      (libsource (lib "eagle-import") (part "PC817XI"))
    )
    (comp (ref "X3")
      (value "GMSTBV3")
      (footprint "eagle-import:GMSTBV3")
      (fields (field (name "MPN") "GMSTBVA2,5/3-G-7,62"))
      (libsource (lib "eagle-import") (part "con-phoenix-762_177_GMSTBV3"))
    )
    (comp (ref "X9")
      (value "22-23-2031")
      (footprint "eagle-import:22-23-2031")
      (fields (field (name "MF") "MOLEX"))
      (libsource (lib "eagle-import") (part "22-23-2031"))
    )
    (comp (ref "X10")
      (value "22-23-2031")
      (footprint "eagle-import:22-23-2031")
      (fields (field (name "MF") "MOLEX"))
      (libsource (lib "eagle-import") (part "22-23-2031"))
    )
    (comp (ref "X4")
      (value "2540-")
      (footprint "eagle-import:PAK100_2500-40")
      (libsource (lib "eagle-import") (part "2540-"))
    )
  )
  (nets
    (net (code "1") (name "+3V3_LG") (class "Default")
      (node (ref "C40") (pin "1") (pinfunction "1_1") (pintype "passive"))
      (node (ref "C51(100UF)") (pin "+") (pinfunction "+_+") (pintype "passive"))
      (node (ref "C52(0.1UF)") (pin "1") (pinfunction "1_1") (pintype "passive"))
      (node (ref "C64") (pin "+") (pinfunction "+_+") (pintype "passive"))
      (node (ref "C65") (pin "1") (pinfunction "1_1") (pintype "passive"))
      (node (ref "PS2_3.3V") (pin "3") (pinfunction "+VOUT_3") (pintype "output"))
      (node (ref "R27") (pin "2") (pinfunction "2_2") (pintype "passive"))
      (node (ref "R29") (pin "2") (pinfunction "2_2") (pintype "passive"))
      (node (ref "R34") (pin "2") (pinfunction "2_2") (pintype "passive"))
      (node (ref "R4") (pin "2") (pinfunction "2_2") (pintype "passive"))
      (node (ref "R41") (pin "2") (pinfunction "2_2") (pintype "passive"))
      (node (ref "U12") (pin "16") (pinfunction "VCC_16") (pintype "output"))
      (node (ref "U12") (pin "4") (pinfunction "EN_4") (pintype "output"))
      (node (ref "U13") (pin "1") (pinfunction "VDD1_1") (pintype "power_in"))
      (node (ref "U15") (pin "16") (pinfunction "VCC_16") (pintype "output"))
      (node (ref "U15") (pin "4") (pinfunction "EN_4") (pintype "output"))
      (node (ref "U17") (pin "1") (pinfunction "VDD1_1") (pintype "power_in"))
      (node (ref "U18") (pin "16") (pinfunction "VCC_16") (pintype "output"))
      (node (ref "U18") (pin "4") (pinfunction "EN_4") (pintype "output"))
      (node (ref "U19") (pin "16") (pinfunction "VCC_16") (pintype "output"))
      (node (ref "U19") (pin "4") (pinfunction "EN_4") (pintype "output"))
      (node (ref "U2") (pin "23") (pinfunction "DVDD_23") (pintype "power_in"))
      (node (ref "U2") (pin "34") (pinfunction "REFSEL_34") (pintype "input"))
      (node (ref "U2") (pin "6") (pinfunction "~{PAR/}SER/BYTESEL_6") (pintype "input"))
      (node (ref "U2") (pin "7") (pinfunction "~{STBY}_7") (pintype "bidirectional"))
      (node (ref "U20") (pin "16") (pinfunction "VCC_16") (pintype "output"))
      (node (ref "U20") (pin "4") (pinfunction "EN_4") (pintype "output"))
      (node (ref "X2") (pin "3") (pinfunction "KL_3") (pintype "passive"))
    )
    (net (code "2") (name "+4.3V_LG") (class "Default")
      (node (ref "C19") (pin "1") (pinfunction "1_1") (pintype "passive"))
      (node (ref "D3") (pin "C") (pinfunction "C_C") (pintype "passive"))
      (node (ref "R25") (pin "1") (pinfunction "1_1") (pintype "passive"))
      (node (ref "U3") (pin "5") (pinfunction "-IN_5") (pintype "input"))
      (node (ref "U6") (pin "5") (pinfunction "-IN_5") (pintype "input"))
    )
    (net (code "3") (name "+5V_LG") (class "Default")
      (node (ref "C10_100UF") (pin "+") (pinfunction "+_+") (pintype "passive"))
      (node (ref "C12") (pin "1") (pinfunction "1_1") (pintype "passive"))
      (node (ref "C16") (pin "1") (pinfunction "1_1") (pintype "passive"))
      (node (ref "C2") (pin "1") (pinfunction "1_1") (pintype "passive"))
      (node (ref "C29") (pin "1") (pinfunction "1_1") (pintype "passive"))
      (node (ref "C30") (pin "1") (pinfunction "1_1") (pintype "passive"))
      (node (ref "C34") (pin "1") (pinfunction "1_1") (pintype "passive"))
      (node (ref "C35") (pin "1") (pinfunction "1_1") (pintype "passive"))
      (node (ref "C61") (pin "1") (pinfunction "1_1") (pintype "passive"))
      (node (ref "PS1_5V") (pin "3") (pinfunction "+VOUT_3") (pintype "output"))
      (node (ref "U$12") (pin "6") (pinfunction "VREF_6") (pintype "bidirectional"))
      (node (ref "U$12") (pin "8") (pinfunction "VDD2_8") (pintype "bidirectional"))
      (node (ref "U$5") (pin "15") (pinfunction "+UC_15") (pintype "bidirectional"))
      (node (ref "U$7") (pin "15") (pinfunction "+UC_15") (pintype "bidirectional"))
      (node (ref "U2") (pin "1") (pinfunction "AVDD_1") (pintype "power_in"))
      (node (ref "U2") (pin "37") (pinfunction "AVDD_37") (pintype "power_in"))
      (node (ref "U2") (pin "38") (pinfunction "AVDD_38") (pintype "power_in"))
      (node (ref "U2") (pin "48") (pinfunction "AVDD_48") (pintype "power_in"))
      (node (ref "X2") (pin "6") (pinfunction "KL_6") (pintype "passive"))
    )
    (net (code "4") (name "+5V_PG") (class "Default")
      (node (ref "C45_10UF") (pin "+") (pinfunction "+_+") (pintype "passive"))
      (node (ref "C50_100NF") (pin "1") (pinfunction "1_1") (pintype "passive"))
      (node (ref "C58") (pin "1") (pinfunction "1_1") (pintype "passive"))
      (node (ref "PS5_5V") (pin "3") (pinfunction "+VOUT_3") (pintype "output"))
      (node (ref "R2") (pin "2") (pinfunction "2_2") (pintype "passive"))
      (node (ref "R35") (pin "2") (pinfunction "2_2") (pintype "passive"))
      (node (ref "R42") (pin "2") (pinfunction "2_2") (pintype "passive"))
      (node (ref "TP2") (pin "TP") (pinfunction "TP_TP") (pintype "input"))
      (node (ref "U$12") (pin "1") (pinfunction "VDD1_1") (pintype "bidirectional"))
      (node (ref "U13") (pin "16") (pinfunction "VDD2_16") (pintype "power_in"))
      (node (ref "U17") (pin "16") (pinfunction "VDD2_16") (pintype "power_in"))
    )
    (net (code "5") (name "+12V_LG") (class "Default")
      (node (ref "C13_0.1UF") (pin "1") (pinfunction "1_1") (pintype "passive"))
      (node (ref "C21") (pin "1") (pinfunction "1_1") (pintype "passive"))
      (node (ref "C43") (pin "1") (pinfunction "1_1") (pintype "passive"))
      (node (ref "C9_100UF") (pin "+") (pinfunction "+_+") (pintype "passive"))
      (node (ref "IC1") (pin "8") (pinfunction "V+_8") (pintype "power_in"))
      (node (ref "PS3_12V") (pin "3") (pinfunction "+VOUT_3") (pintype "output"))
      (node (ref "R12") (pin "2") (pinfunction "2_2") (pintype "passive"))
      (node (ref "R14") (pin "2") (pinfunction "2_2") (pintype "passive"))
      (node (ref "R23") (pin "2") (pinfunction "2_2") (pintype "passive"))
      (node (ref "R24") (pin "2") (pinfunction "2_2") (pintype "passive"))
      (node (ref "R25") (pin "2") (pinfunction "2_2") (pintype "passive"))
      (node (ref "U3") (pin "11") (pinfunction "V+_11") (pintype "power_in"))
      (node (ref "X2") (pin "5") (pinfunction "KL_5") (pintype "passive"))
    )
    (net (code "6") (name "+15V_PG") (class "Default")
      (node (ref "C36_100NF") (pin "1") (pinfunction "1_1") (pintype "passive"))
      (node (ref "C37") (pin "+") (pinfunction "+_+") (pintype "passive"))
      (node (ref "C37_10UF") (pin "+") (pinfunction "+_+") (pintype "passive"))
      (node (ref "C45") (pin "1") (pinfunction "1_1") (pintype "passive"))
      (node (ref "IC3") (pin "2") (pinfunction "VDD_2") (pintype "bidirectional"))
      (node (ref "PS6_15V") (pin "3") (pinfunction "+VOUT_3") (pintype "output"))
      (node (ref "R30") (pin "2") (pinfunction "2_2") (pintype "passive"))
      (node (ref "R5") (pin "1") (pinfunction "1_1") (pintype "passive"))
      (node (ref "TP1") (pin "TP") (pinfunction "TP_TP") (pintype "input"))
    )
    (net (code "7") (name "+24V") (class "Default")
      (node (ref "C4") (pin "+") (pinfunction "+_+") (pintype "passive"))
      (node (ref "K1") (pin "2") (pinfunction "COM_2") (pintype "bidirectional"))
      (node (ref "X1") (pin "1") (pinfunction "KL_1") (pintype "passive"))
    )
    (net (code "8") (name "-4.3V_LG") (class "Default")
      (node (ref "C20") (pin "1") (pinfunction "1_1") (pintype "passive"))
      (node (ref "D4") (pin "A") (pinfunction "A_A") (pintype "passive"))
      (node (ref "R26") (pin "1") (pinfunction "1_1") (pintype "passive"))
      (node (ref "U3") (pin "9") (pinfunction "+IN2_9") (pintype "input"))
      (node (ref "U6") (pin "9") (pinfunction "+IN2_9") (pintype "input"))
    )
    (net (code "9") (name "-12V_LG") (class "Default")
      (node (ref "C11_0.1UF") (pin "1") (pinfunction "1_1") (pintype "passive"))
      (node (ref "C22") (pin "1") (pinfunction "1_1") (pintype "passive"))
      (node (ref "C44") (pin "1") (pinfunction "1_1") (pintype "passive"))
      (node (ref "C7") (pin "-") (pinfunction "-_-") (pintype "passive"))
      (node (ref "C8_100UF") (pin "-") (pinfunction "-_-") (pintype "passive"))
      (node (ref "IC1") (pin "4") (pinfunction "V-_4") (pintype "power_in"))
      (node (ref "PS4_12V") (pin "2") (pinfunction "GND_2") (pintype "power_in"))
      (node (ref "R26") (pin "2") (pinfunction "2_2") (pintype "passive"))
      (node (ref "U3") (pin "6") (pinfunction "V-_6") (pintype "power_in"))
      (node (ref "X2") (pin "4") (pinfunction "KL_4") (pintype "passive"))
    )
    (net (code "10") (name "ADC_BUSY") (class "Default")
      (node (ref "U12") (pin "7") (pinfunction "IN_7") (pintype "input"))
      (node (ref "U2") (pin "14") (pinfunction "BUSY_14") (pintype "output"))
    )
    (net (code "11") (name "ADC_BUSY_DIFF_A") (class "Default")
      (node (ref "U12") (pin "6") (pinfunction "A_6") (pintype "output"))
      (node (ref "X4") (pin "17") (pinfunction "KL_17") (pintype "passive"))
    )
    (net (code "12") (name "ADC_BUSY_DIFF_B") (class "Default")
      (node (ref "U12") (pin "5") (pinfunction "B_5") (pintype "output"))
      (node (ref "X4") (pin "19") (pinfunction "KL_19") (pintype "passive"))
    )
    (net (code "13") (name "ADC_CONVST_DIFF") (class "Default")
      (node (ref "U15") (pin "11") (pinfunction "OUT_11") (pintype "output"))
      (node (ref "U2") (pin "10") (pinfunction "CONVSTB_10") (pintype "input"))
      (node (ref "U2") (pin "9") (pinfunction "CONVSTA_9") (pintype "input"))
    )
    (net (code "14") (name "ADC_CONVST_DIFF_A") (class "Default")
      (node (ref "U15") (pin "10") (pinfunction "A_10") (pintype "input"))
      (node (ref "X4") (pin "13") (pinfunction "KL_13") (pintype "passive"))
    )
    (net (code "15") (name "ADC_CONVST_DIFF_B") (class "Default")
      (node (ref "U15") (pin "9") (pinfunction "B_9") (pintype "input"))
      (node (ref "X4") (pin "15") (pinfunction "KL_15") (pintype "passive"))
    )
    (net (code "16") (name "ADC_CS_DIFF") (class "Default")
      (node (ref "U15") (pin "13") (pinfunction "OUT_13") (pintype "output"))
      (node (ref "U2") (pin "13") (pinfunction "~{CS}_13") (pintype "input"))
    )
    (net (code "17") (name "ADC_CS_DIFF_A") (class "Default")
      (node (ref "U15") (pin "14") (pinfunction "A_14") (pintype "input"))
      (node (ref "X4") (pin "11") (pinfunction "KL_11") (pintype "passive"))
    )
    (net (code "18") (name "ADC_CS_DIFF_B") (class "Default")
      (node (ref "U15") (pin "15") (pinfunction "B_15") (pintype "input"))
      (node (ref "X4") (pin "9") (pinfunction "KL_9") (pintype "passive"))
    )
    (net (code "19") (name "ADC_DOUT0") (class "Default")
      (node (ref "U12") (pin "9") (pinfunction "IN_9") (pintype "input"))
      (node (ref "U2") (pin "24") (pinfunction "DB7/DOUTA_24") (pintype "output"))
    )
    (net (code "20") (name "ADC_DOUT0_DIFF_A") (class "Default")
      (node (ref "U12") (pin "10") (pinfunction "A_10") (pintype "output"))
      (node (ref "X4") (pin "27") (pinfunction "KL_27") (pintype "passive"))
    )
    (net (code "21") (name "ADC_DOUT0_DIFF_B") (class "Default")
      (node (ref "U12") (pin "11") (pinfunction "B_11") (pintype "output"))
      (node (ref "X4") (pin "25") (pinfunction "KL_25") (pintype "passive"))
    )
    (net (code "22") (name "ADC_DOUT1") (class "Default")
      (node (ref "U12") (pin "1") (pinfunction "IN_1") (pintype "input"))
      (node (ref "U2") (pin "25") (pinfunction "DB8/DOUTB_25") (pintype "output"))
    )
    (net (code "23") (name "ADC_DOUT1_DIFF_A") (class "Default")
      (node (ref "U12") (pin "2") (pinfunction "A_2") (pintype "output"))
      (node (ref "X4") (pin "21") (pinfunction "KL_21") (pintype "passive"))
    )
    (net (code "24") (name "ADC_DOUT1_DIFF_B") (class "Default")
      (node (ref "U12") (pin "3") (pinfunction "B_3") (pintype "output"))
      (node (ref "X4") (pin "23") (pinfunction "KL_23") (pintype "passive"))
    )
    (net (code "25") (name "ADC_RESET_DIFF") (class "Default")
      (node (ref "U15") (pin "5") (pinfunction "OUT_5") (pintype "output"))
      (node (ref "U2") (pin "11") (pinfunction "RESET_11") (pintype "input"))
    )
    (net (code "26") (name "ADC_RESET_DIFF_A") (class "Default")
      (node (ref "U15") (pin "6") (pinfunction "A_6") (pintype "input"))
      (node (ref "X4") (pin "3") (pinfunction "KL_3") (pintype "passive"))
    )
    (net (code "27") (name "ADC_RESET_DIFF_B") (class "Default")
      (node (ref "U15") (pin "7") (pinfunction "B_7") (pintype "input"))
      (node (ref "X4") (pin "1") (pinfunction "KL_1") (pintype "passive"))
    )
    (net (code "28") (name "ADC_SCLK_DIFF") (class "Default")
      (node (ref "U15") (pin "3") (pinfunction "OUT_3") (pintype "output"))
      (node (ref "U2") (pin "12") (pinfunction "~{RD}/SCLK_12") (pintype "input"))
    )
    (net (code "29") (name "ADC_SCLK_DIFF_A") (class "Default")
      (node (ref "U15") (pin "2") (pinfunction "A_2") (pintype "input"))
      (node (ref "X4") (pin "5") (pinfunction "KL_5") (pintype "passive"))
    )
    (net (code "30") (name "ADC_SCLK_DIFF_B") (class "Default")
      (node (ref "U15") (pin "1") (pinfunction "B_1") (pintype "input"))
      (node (ref "X4") (pin "7") (pinfunction "KL_7") (pintype "passive"))
    )
    (net (code "31") (name "BRAKE_SIGNAL") (class "Default")
      (node (ref "T1") (pin "B") (pinfunction "B_B") (pintype "passive"))
    )
    (net (code "32") (name "BRK+") (class "Default")
      (node (ref "K1") (pin "3") (pinfunction "NO_3") (pintype "bidirectional"))
      (node (ref "X5") (pin "1") (pinfunction "KL_1") (pintype "passive"))
    )
    (net (code "33") (name "COIL+") (class "Default")
      (node (ref "K1") (pin "1") (pinfunction "COIL_1_1") (pintype "bidirectional"))
      (node (ref "T1") (pin "E") (pinfunction "E_E") (pintype "passive"))
    )
    (net (code "34") (name "DC+") (class "Default")
      (node (ref "C53") (pin "+") (pinfunction "+_+") (pintype "passive"))
      (node (ref "C54") (pin "+") (pinfunction "+_+") (pintype "passive"))
      (node (ref "C55") (pin "+") (pinfunction "+_+") (pintype "passive"))
      (node (ref "C56") (pin "1") (pinfunction "1_1") (pintype "passive"))
      (node (ref "C62") (pin "+") (pinfunction "+_+") (pintype "passive"))
      (node (ref "IC3") (pin "38") (pinfunction "P_38") (pintype "bidirectional"))
      (node (ref "K2") (pin "8") (pinfunction "NO_1_8") (pintype "bidirectional"))
      (node (ref "K2") (pin "9") (pinfunction "NO_2_9") (pintype "bidirectional"))
      (node (ref "R37") (pin "2") (pinfunction "2_2") (pintype "passive"))
      (node (ref "R39") (pin "2") (pinfunction "2_2") (pintype "passive"))
    )
    (net (code "35") (name "DC-") (class "Default")
      (node (ref "C53") (pin "-") (pinfunction "-_-") (pintype "passive"))
      (node (ref "C54") (pin "-") (pinfunction "-_-") (pintype "passive"))
      (node (ref "C55") (pin "-") (pinfunction "-_-") (pintype "passive"))
      (node (ref "C56") (pin "2") (pinfunction "2_2") (pintype "passive"))
      (node (ref "C62") (pin "-") (pinfunction "-_-") (pintype "passive"))
      (node (ref "IC3") (pin "17") (pinfunction "NU_17") (pintype "bidirectional"))
      (node (ref "IC3") (pin "18") (pinfunction "NV_18") (pintype "bidirectional"))
      (node (ref "IC3") (pin "19") (pinfunction "NW_19") (pintype "bidirectional"))
      (node (ref "R38") (pin "1") (pinfunction "1_1") (pintype "passive"))
      (node (ref "U$16") (pin "P$2") (pinfunction "-_P$2") (pintype "bidirectional"))
      (node (ref "U$2") (pin "1") (pinfunction "1_1") (pintype "passive"))
    )
    (net (code "36") (name "EARTH") (class "Default")
      (node (ref "U$14") (pin "1") (pinfunction "1_1") (pintype "bidirectional"))
      (node (ref "U$15") (pin "1") (pinfunction "1_1") (pintype "bidirectional"))
      (node (ref "X7") (pin "3") (pinfunction "1_3") (pintype "passive"))
    )
    (net (code "37") (name "GND") (class "Default")
      (node (ref "C4") (pin "-") (pinfunction "-_-") (pintype "passive"))
      (node (ref "X1") (pin "2") (pinfunction "KL_2") (pintype "passive"))
      (node (ref "X5") (pin "2") (pinfunction "KL_2") (pintype "passive"))
    )
    (net (code "38") (name "IPM_FAULT_LG") (class "Default")
      (node (ref "R4") (pin "1") (pinfunction "1_1") (pintype "passive"))
      (node (ref "U20") (pin "1") (pinfunction "IN_1") (pintype "input"))
      (node (ref "U21") (pin "4") (pinfunction "CT_4") (pintype "passive"))
    )
    (net (code "39") (name "IPM_FAULT_LG_DIFF_A") (class "Default")
      (node (ref "U20") (pin "2") (pinfunction "A_2") (pintype "output"))
      (node (ref "X4") (pin "30") (pinfunction "KL_30") (pintype "passive"))
    )
    (net (code "40") (name "IPM_FAULT_LG_DIFF_B") (class "Default")
      (node (ref "U20") (pin "3") (pinfunction "B_3") (pintype "output"))
      (node (ref "X4") (pin "32") (pinfunction "KL_32") (pintype "passive"))
    )
    (net (code "41") (name "IPM_FAULT_PG") (class "Default")
      (node (ref "IC3") (pin "9") (pinfunction "FAULT_9") (pintype "bidirectional"))
      (node (ref "U21") (pin "2") (pinfunction "C_2") (pintype "passive"))
    )
    (net (code "42") (name "IPM_ITRIP_PG") (class "Default")
      (node (ref "IC3") (pin "10") (pinfunction "ITRIP_10") (pintype "bidirectional"))
    )
    (net (code "43") (name "IPM_SD_LG") (class "Default")
      (node (ref "R34") (pin "1") (pinfunction "1_1") (pintype "passive"))
      (node (ref "U18") (pin "11") (pinfunction "OUT_11") (pintype "output"))
      (node (ref "U22") (pin "1") (pinfunction "A_1") (pintype "passive"))
    )
    (net (code "44") (name "IPM_SD_LG_DIFF_A") (class "Default")
      (node (ref "U18") (pin "10") (pinfunction "A_10") (pintype "input"))
      (node (ref "X4") (pin "16") (pinfunction "KL_16") (pintype "passive"))
    )
    (net (code "45") (name "IPM_SD_LG_DIFF_B") (class "Default")
      (node (ref "U18") (pin "9") (pinfunction "B_9") (pintype "input"))
      (node (ref "X4") (pin "14") (pinfunction "KL_14") (pintype "passive"))
    )
    (net (code "46") (name "IPM_SD_PG") (class "Default")
      (node (ref "IC3") (pin "11") (pinfunction "SD_11") (pintype "bidirectional"))
      (node (ref "R35") (pin "1") (pinfunction "1_1") (pintype "passive"))
      (node (ref "U22") (pin "4") (pinfunction "CT_4") (pintype "passive"))
    )
    (net (code "47") (name "I_U") (class "Default")
      (node (ref "R13") (pin "1") (pinfunction "1_1") (pintype "passive"))
      (node (ref "U$5") (pin "13") (pinfunction "VOUT_13") (pintype "bidirectional"))
    )
    (net (code "48") (name "I_U_ADC") (class "Default")
      (node (ref "IC1") (pin "7") (pinfunction "OUT_7") (pintype "output"))
      (node (ref "R8") (pin "2") (pinfunction "2_2") (pintype "passive"))
      (node (ref "U2") (pin "49") (pinfunction "AIN_1P_49") (pintype "input"))
      (node (ref "U3") (pin "10") (pinfunction "-IN2_10") (pintype "input"))
      (node (ref "U3") (pin "4") (pinfunction "+IN_4") (pintype "input"))
    )
    (net (code "49") (name "I_U_SCT_FAULT") (class "Default")
      (node (ref "R27") (pin "1") (pinfunction "1_1") (pintype "passive"))
      (node (ref "U3") (pin "12") (pinfunction "OUT1_12") (pintype "output"))
      (node (ref "U3") (pin "7") (pinfunction "OUT2_7") (pintype "output"))
      (node (ref "U9") (pin "7") (pinfunction "IN_7") (pintype "input"))
    )
    (net (code "50") (name "I_U_SCT_FAULT_DIFF_A") (class "Default")
      (node (ref "U9") (pin "6") (pinfunction "A_6") (pintype "output"))
      (node (ref "X4") (pin "31") (pinfunction "KL_31") (pintype "passive"))
    )
    (net (code "51") (name "I_U_SCT_FAULT_DIFF_B") (class "Default")
      (node (ref "U9") (pin "5") (pinfunction "B_5") (pintype "output"))
      (node (ref "X4") (pin "29") (pinfunction "KL_29") (pintype "passive"))
    )
    (net (code "52") (name "I_W") (class "Default")
      (node (ref "R20") (pin "1") (pinfunction "1_1") (pintype "passive"))
      (node (ref "U$7") (pin "13") (pinfunction "VOUT_13") (pintype "bidirectional"))
    )
    (net (code "53") (name "I_W_ADC") (class "Default")
      (node (ref "IC4") (pin "7") (pinfunction "OUT_7") (pintype "output"))
      (node (ref "R15") (pin "2") (pinfunction "2_2") (pintype "passive"))
      (node (ref "U2") (pin "57") (pinfunction "AIN_3P_57") (pintype "input"))
      (node (ref "U6") (pin "10") (pinfunction "-IN2_10") (pintype "input"))
      (node (ref "U6") (pin "4") (pinfunction "+IN_4") (pintype "input"))
    )
    (net (code "54") (name "I_W_SCT_FAULT") (class "Default")
      (node (ref "R29") (pin "1") (pinfunction "1_1") (pintype "passive"))
      (node (ref "U6") (pin "12") (pinfunction "OUT1_12") (pintype "output"))
      (node (ref "U6") (pin "7") (pinfunction "OUT2_7") (pintype "output"))
      (node (ref "U9") (pin "15") (pinfunction "IN_15") (pintype "input"))
    )
    (net (code "55") (name "I_W_SCT_FAULT_DIFF_A") (class "Default")
      (node (ref "U9") (pin "14") (pinfunction "A_14") (pintype "output"))
      (node (ref "X4") (pin "33") (pinfunction "KL_33") (pintype "passive"))
    )
    (net (code "56") (name "I_W_SCT_FAULT_DIFF_B") (class "Default")
      (node (ref "U9") (pin "13") (pinfunction "B_13") (pintype "output"))
      (node (ref "X4") (pin "34") (pinfunction "KL_34") (pintype "passive"))
      (node (ref "X4") (pin "35") (pinfunction "KL_35") (pintype "passive"))
    )
    (net (code "57") (name "LG") (class "Default")
      (node (ref "B1") (pin "-") (pinfunction "-_-") (pintype "passive"))
      (node (ref "B4_MB6S") (pin "-") (pinfunction "-_-") (pintype "passive"))
      (node (ref "B5") (pin "-") (pinfunction "-_-") (pintype "passive"))
      (node (ref "C1") (pin "-") (pinfunction "-_-") (pintype "passive"))
      (node (ref "C10_100UF") (pin "-") (pinfunction "-_-") (pintype "passive"))
      (node (ref "C11_0.1UF") (pin "2") (pinfunction "2_2") (pintype "passive"))
      (node (ref "C12") (pin "2") (pinfunction "2_2") (pintype "passive"))
      (node (ref "C13_0.1UF") (pin "2") (pinfunction "2_2") (pintype "passive"))
      (node (ref "C16") (pin "2") (pinfunction "2_2") (pintype "passive"))
      (node (ref "C19") (pin "2") (pinfunction "2_2") (pintype "passive"))
      (node (ref "C2") (pin "2") (pinfunction "2_2") (pintype "passive"))
      (node (ref "C20") (pin "2") (pinfunction "2_2") (pintype "passive"))
      (node (ref "C21") (pin "2") (pinfunction "2_2") (pintype "passive"))
      (node (ref "C22") (pin "2") (pinfunction "2_2") (pintype "passive"))
      (node (ref "C29") (pin "2") (pinfunction "2_2") (pintype "passive"))
      (node (ref "C2_10UF") (pin "-") (pinfunction "-_-") (pintype "passive"))
      (node (ref "C30") (pin "2") (pinfunction "2_2") (pintype "passive"))
      (node (ref "C34") (pin "2") (pinfunction "2_2") (pintype "passive"))
      (node (ref "C35") (pin "2") (pinfunction "2_2") (pintype "passive"))
      (node (ref "C38") (pin "2") (pinfunction "2_2") (pintype "passive"))
      (node (ref "C39") (pin "2") (pinfunction "2_2") (pintype "passive"))
      (node (ref "C40") (pin "2") (pinfunction "2_2") (pintype "passive"))
      (node (ref "C41") (pin "2") (pinfunction "2_2") (pintype "passive"))
      (node (ref "C42") (pin "1") (pinfunction "1_1") (pintype "passive"))
      (node (ref "C43") (pin "2") (pinfunction "2_2") (pintype "passive"))
      (node (ref "C44") (pin "2") (pinfunction "2_2") (pintype "passive"))
      (node (ref "C51(100UF)") (pin "-") (pinfunction "-_-") (pintype "passive"))
      (node (ref "C52(0.1UF)") (pin "2") (pinfunction "2_2") (pintype "passive"))
      (node (ref "C60") (pin "2") (pinfunction "2_2") (pintype "bidirectional"))
      (node (ref "C61") (pin "2") (pinfunction "2_2") (pintype "passive"))
      (node (ref "C64") (pin "-") (pinfunction "-_-") (pintype "passive"))
      (node (ref "C65") (pin "2") (pinfunction "2_2") (pintype "passive"))
      (node (ref "C8_100UF") (pin "+") (pinfunction "+_+") (pintype "passive"))
      (node (ref "C9_100UF") (pin "-") (pinfunction "-_-") (pintype "passive"))
      (node (ref "D3") (pin "A") (pinfunction "A_A") (pintype "passive"))
      (node (ref "D4") (pin "C") (pinfunction "C_C") (pintype "passive"))
      (node (ref "IC2") (pin "A") (pinfunction "A_A") (pintype "passive"))
      (node (ref "IC6") (pin "A") (pinfunction "A_A") (pintype "passive"))
      (node (ref "IC7") (pin "A") (pinfunction "A_A") (pintype "passive"))
      (node (ref "K1") (pin "4") (pinfunction "COIL_2_4") (pintype "bidirectional"))
      (node (ref "PS1_5V") (pin "2") (pinfunction "GND_2") (pintype "power_in"))
      (node (ref "PS2_3.3V") (pin "2") (pinfunction "GND_2") (pintype "power_in"))
      (node (ref "PS3_12V") (pin "2") (pinfunction "GND_2") (pintype "power_in"))
      (node (ref "PS4_12V") (pin "3") (pinfunction "+VOUT_3") (pintype "output"))
      (node (ref "R10") (pin "2") (pinfunction "2_2") (pintype "passive"))
      (node (ref "R11") (pin "2") (pinfunction "2_2") (pintype "passive"))
      (node (ref "R21") (pin "2") (pinfunction "2_2") (pintype "passive"))
      (node (ref "U$12") (pin "5") (pinfunction "GND2_5") (pintype "bidirectional"))
      (node (ref "U$5") (pin "14") (pinfunction "GND_14") (pintype "bidirectional"))
      (node (ref "U$7") (pin "14") (pinfunction "GND_14") (pintype "bidirectional"))
      (node (ref "U12") (pin "12") (pinfunction "~{EN}_12") (pintype "output"))
      (node (ref "U12") (pin "8") (pinfunction "GND_8") (pintype "output"))
      (node (ref "U13") (pin "2") (pinfunction "~{GND1}_2") (pintype "passive"))
      (node (ref "U13") (pin "8") (pinfunction "~{GND1}_8") (pintype "passive"))
      (node (ref "U15") (pin "12") (pinfunction "~{EN}_12") (pintype "output"))
      (node (ref "U15") (pin "8") (pinfunction "GND_8") (pintype "output"))
      (node (ref "U17") (pin "2") (pinfunction "~{GND1}_2") (pintype "passive"))
      (node (ref "U17") (pin "8") (pinfunction "~{GND1}_8") (pintype "passive"))
      (node (ref "U18") (pin "12") (pinfunction "~{EN}_12") (pintype "output"))
      (node (ref "U18") (pin "8") (pinfunction "GND_8") (pintype "output"))
      (node (ref "U19") (pin "12") (pinfunction "~{EN}_12") (pintype "output"))
      (node (ref "U19") (pin "8") (pinfunction "GND_8") (pintype "output"))
      (node (ref "U2") (pin "2") (pinfunction "AGND_2") (pintype "power_in"))
      (node (ref "U2") (pin "26") (pinfunction "AGND_26") (pintype "power_in"))
      (node (ref "U2") (pin "32") (pinfunction "DB14/HBEN_32") (pintype "bidirectional"))
      (node (ref "U2") (pin "33") (pinfunction "DB15/BYTESEL_33") (pintype "bidirectional"))
      (node (ref "U2") (pin "35") (pinfunction "AGND_35") (pintype "power_in"))
      (node (ref "U2") (pin "40") (pinfunction "AGND_40") (pintype "power_in"))
      (node (ref "U2") (pin "41") (pinfunction "AGND_41") (pintype "power_in"))
      (node (ref "U2") (pin "43") (pinfunction "REFGND_43") (pintype "power_in"))
      (node (ref "U2") (pin "46") (pinfunction "REFGND_46") (pintype "power_in"))
      (node (ref "U2") (pin "47") (pinfunction "AGND_47") (pintype "power_in"))
      (node (ref "U2") (pin "50") (pinfunction "AIN_1GND_50") (pintype "input"))
      (node (ref "U2") (pin "52") (pinfunction "AIN_2GND_52") (pintype "input"))
      (node (ref "U2") (pin "53") (pinfunction "AGND_53") (pintype "power_in"))
      (node (ref "U2") (pin "54") (pinfunction "AGND_54") (pintype "power_in"))
      (node (ref "U2") (pin "55") (pinfunction "AGND_55") (pintype "power_in"))
      (node (ref "U2") (pin "56") (pinfunction "AGND_56") (pintype "power_in"))
      (node (ref "U2") (pin "58") (pinfunction "AIN_3GND_58") (pintype "input"))
      (node (ref "U2") (pin "60") (pinfunction "AIN_4GND_60") (pintype "input"))
      (node (ref "U2") (pin "61") (pinfunction "AGND_61") (pintype "power_in"))
      (node (ref "U2") (pin "62") (pinfunction "AGND_62") (pintype "power_in"))
      (node (ref "U2") (pin "63") (pinfunction "AGND_63") (pintype "power_in"))
      (node (ref "U2") (pin "64") (pinfunction "AGND_64") (pintype "power_in"))
      (node (ref "U2") (pin "8") (pinfunction "RANGE_8") (pintype "input"))
      (node (ref "U20") (pin "12") (pinfunction "~{EN}_12") (pintype "output"))
      (node (ref "U20") (pin "8") (pinfunction "GND_8") (pintype "output"))
      (node (ref "U21") (pin "3") (pinfunction "ET_3") (pintype "passive"))
      (node (ref "U22") (pin "2") (pinfunction "C_2") (pintype "passive"))
      (node (ref "U3") (pin "3") (pinfunction "GND1_3") (pintype "power_in"))
      (node (ref "U3") (pin "8") (pinfunction "GND2_8") (pintype "power_in"))
      (node (ref "U6") (pin "3") (pinfunction "GND1_3") (pintype "power_in"))
      (node (ref "U6") (pin "8") (pinfunction "GND2_8") (pintype "power_in"))
      (node (ref "X2") (pin "2") (pinfunction "KL_2") (pintype "passive"))
    )
    (net (code "58") (name "LINE") (class "Default")
      (node (ref "U$1") (pin "P$1") (pinfunction "AC1_P$1") (pintype "bidirectional"))
      (node (ref "U$13") (pin "1") (pinfunction "1_1") (pintype "bidirectional"))
      (node (ref "U$15") (pin "2") (pinfunction "2_2") (pintype "bidirectional"))
      (node (ref "X7") (pin "1") (pinfunction "1_1") (pintype "passive"))
    )
    (net (code "59") (name "LM_U") (class "Default")
      (node (ref "IC2") (pin "C") (pinfunction "C_C") (pintype "passive"))
      (node (ref "X9") (pin "3") (pinfunction "S_3") (pintype "passive"))
    )
    (net (code "60") (name "LM_W") (class "Default")
      (node (ref "IC6") (pin "C") (pinfunction "C_C") (pintype "passive"))
      (node (ref "X10") (pin "3") (pinfunction "S_3") (pintype "passive"))
    )
    (net (code "61") (name "NEUTRAL") (class "Default")
      (node (ref "U$1") (pin "P$3") (pinfunction "AC2_P$3") (pintype "bidirectional"))
      (node (ref "U$13") (pin "2") (pinfunction "2_2") (pintype "bidirectional"))
      (node (ref "U$14") (pin "2") (pinfunction "2_2") (pintype "bidirectional"))
      (node (ref "X7") (pin "2") (pinfunction "1_2") (pintype "passive"))
    )
    (net (code "62") (name "Net-(B1-AC1)") (class "Default")
      (node (ref "B1") (pin "~1") (pinfunction "AC1_~1") (pintype "passive"))
      (node (ref "U$1") (pin "P$8") (pinfunction "12V1B_P$8") (pintype "bidirectional"))
    )
    (net (code "63") (name "Net-(B1-AC2)") (class "Default")
      (node (ref "B1") (pin "~2") (pinfunction "AC2_~2") (pintype "passive"))
      (node (ref "U$1") (pin "P$7") (pinfunction "12V1A_P$7") (pintype "bidirectional"))
    )
    (net (code "64") (name "Net-(B4_MB6S-AC1)") (class "Default")
      (node (ref "B4_MB6S") (pin "~1") (pinfunction "AC1_~1") (pintype "passive"))
      (node (ref "U$1") (pin "P$6") (pinfunction "5V2_P$6") (pintype "bidirectional"))
    )
    (net (code "65") (name "Net-(B4_MB6S-AC2)") (class "Default")
      (node (ref "B4_MB6S") (pin "~2") (pinfunction "AC2_~2") (pintype "passive"))
      (node (ref "U$1") (pin "P$5") (pinfunction "5V1_P$5") (pintype "bidirectional"))
    )
    (net (code "66") (name "Net-(B5-AC1)") (class "Default")
      (node (ref "B5") (pin "~1") (pinfunction "AC1_~1") (pintype "passive"))
      (node (ref "U$1") (pin "P$10") (pinfunction "12V2B_P$10") (pintype "bidirectional"))
    )
    (net (code "67") (name "Net-(B5-AC2)") (class "Default")
      (node (ref "B5") (pin "~2") (pinfunction "AC2_~2") (pintype "passive"))
      (node (ref "U$1") (pin "P$9") (pinfunction "12V2A_P$9") (pintype "bidirectional"))
    )
    (net (code "68") (name "Net-(IC1A-+IN)") (class "Default")
      (node (ref "IC1") (pin "3") (pinfunction "+IN_3") (pintype "input"))
      (node (ref "R11") (pin "1") (pinfunction "1_1") (pintype "passive"))
      (node (ref "R7") (pin "2") (pinfunction "2_2") (pintype "passive"))
    )
    (net (code "69") (name "Net-(IC1A--IN)") (class "Default")
      (node (ref "IC1") (pin "2") (pinfunction "-IN_2") (pintype "input"))
      (node (ref "R3") (pin "1") (pinfunction "1_1") (pintype "passive"))
      (node (ref "R6") (pin "2") (pinfunction "2_2") (pintype "passive"))
    )
    (net (code "70") (name "Net-(IC1B-+IN)") (class "Default")
      (node (ref "IC1") (pin "5") (pinfunction "+IN_5") (pintype "input"))
      (node (ref "R10") (pin "1") (pinfunction "1_1") (pintype "passive"))
      (node (ref "R13") (pin "2") (pinfunction "2_2") (pintype "passive"))
    )
    (net (code "71") (name "Net-(IC1B--IN)") (class "Default")
      (node (ref "IC1") (pin "6") (pinfunction "-IN_6") (pintype "input"))
      (node (ref "R8") (pin "1") (pinfunction "1_1") (pintype "passive"))
      (node (ref "R9") (pin "2") (pinfunction "2_2") (pintype "passive"))
    )
    (net (code "72") (name "Net-(IC3-CFOD)") (class "Default")
      (node (ref "C36") (pin "1") (pinfunction "1_1") (pintype "passive"))
      (node (ref "IC3") (pin "12") (pinfunction "CFOD_12") (pintype "bidirectional"))
      (node (ref "R30") (pin "1") (pinfunction "1_1") (pintype "passive"))
    )
    (net (code "73") (name "Net-(IC3-VB(U))") (class "Default")
      (node (ref "C32") (pin "+") (pinfunction "+_+") (pintype "passive"))
      (node (ref "C33") (pin "1") (pinfunction "1_1") (pintype "passive"))
      (node (ref "IC3") (pin "34") (pinfunction "VB(U)_34") (pintype "bidirectional"))
    )
    (net (code "74") (name "Net-(IC3-VB(V))") (class "Default")
      (node (ref "C46") (pin "+") (pinfunction "+_+") (pintype "passive"))
      (node (ref "C47") (pin "1") (pinfunction "1_1") (pintype "passive"))
      (node (ref "IC3") (pin "28") (pinfunction "VB(V)_28") (pintype "bidirectional"))
    )
    (net (code "75") (name "Net-(IC3-VB(W))") (class "Default")
      (node (ref "C48") (pin "+") (pinfunction "+_+") (pintype "passive"))
      (node (ref "C49") (pin "1") (pinfunction "1_1") (pintype "passive"))
      (node (ref "IC3") (pin "22") (pinfunction "VB(W)_22") (pintype "bidirectional"))
    )
    (net (code "76") (name "Net-(IC3-VS(U),_U)") (class "Default")
      (node (ref "C32") (pin "-") (pinfunction "-_-") (pintype "passive"))
      (node (ref "C33") (pin "2") (pinfunction "2_2") (pintype "passive"))
      (node (ref "IC3") (pin "32") (pinfunction "VS(U),_U_32") (pintype "bidirectional"))
      (node (ref "U$5") (pin "2") (pinfunction "IN2_2") (pintype "bidirectional"))
      (node (ref "U$5") (pin "3") (pinfunction "IN3_3") (pintype "bidirectional"))
      (node (ref "U$5") (pin "4") (pinfunction "IN4_4") (pintype "bidirectional"))
      (node (ref "U$5") (pin "5") (pinfunction "IN5_5") (pintype "bidirectional"))
    )
    (net (code "77") (name "Net-(IC3-VS(W),_W)") (class "Default")
      (node (ref "C48") (pin "-") (pinfunction "-_-") (pintype "passive"))
      (node (ref "C49") (pin "2") (pinfunction "2_2") (pintype "passive"))
      (node (ref "IC3") (pin "20") (pinfunction "VS(W),_W_20") (pintype "bidirectional"))
      (node (ref "U$7") (pin "2") (pinfunction "IN2_2") (pintype "bidirectional"))
      (node (ref "U$7") (pin "3") (pinfunction "IN3_3") (pintype "bidirectional"))
      (node (ref "U$7") (pin "4") (pinfunction "IN4_4") (pintype "bidirectional"))
      (node (ref "U$7") (pin "5") (pinfunction "IN5_5") (pintype "bidirectional"))
    )
    (net (code "78") (name "Net-(IC4B-+IN)") (class "Default")
      (node (ref "IC4") (pin "5") (pinfunction "+IN_5") (pintype "input"))
      (node (ref "R20") (pin "2") (pinfunction "2_2") (pintype "passive"))
      (node (ref "R21") (pin "1") (pinfunction "1_1") (pintype "passive"))
    )
    (net (code "79") (name "Net-(IC4B--IN)") (class "Default")
      (node (ref "IC4") (pin "6") (pinfunction "-IN_6") (pintype "input"))
      (node (ref "R15") (pin "1") (pinfunction "1_1") (pintype "passive"))
      (node (ref "R17") (pin "2") (pinfunction "2_2") (pintype "passive"))
    )
    (net (code "80") (name "Net-(IC7-PadC)") (class "Default")
      (node (ref "IC7") (pin "C") (pinfunction "C_C") (pintype "passive"))
      (node (ref "R24") (pin "1") (pinfunction "1_1") (pintype "passive"))
      (node (ref "R6") (pin "1") (pinfunction "1_1") (pintype "passive"))
    )
    (net (code "81") (name "Net-(K2-+)") (class "Default")
      (node (ref "D2") (pin "C") (pinfunction "C_C") (pintype "passive"))
      (node (ref "K2") (pin "1") (pinfunction "+_1") (pintype "bidirectional"))
      (node (ref "R5") (pin "2") (pinfunction "2_2") (pintype "passive"))
    )
    (net (code "82") (name "Net-(K2--)") (class "Default")
      (node (ref "D2") (pin "A") (pinfunction "A_A") (pintype "passive"))
      (node (ref "K2") (pin "16") (pinfunction "-_16") (pintype "bidirectional"))
      (node (ref "T2") (pin "C") (pinfunction "C_C") (pintype "passive"))
    )
    (net (code "83") (name "Net-(K2-COM_1)") (class "Default")
      (node (ref "K2") (pin "12") (pinfunction "COM_2_12") (pintype "bidirectional"))
      (node (ref "K2") (pin "5") (pinfunction "COM_1_5") (pintype "bidirectional"))
      (node (ref "R39") (pin "1") (pinfunction "1_1") (pintype "passive"))
      (node (ref "U$16") (pin "P$1") (pinfunction "+_P$1") (pintype "bidirectional"))
    )
    (net (code "84") (name "Net-(PS1_5V-+VIN)") (class "Default")
      (node (ref "B4_MB6S") (pin "+") (pinfunction "+_+") (pintype "passive"))
      (node (ref "C1") (pin "+") (pinfunction "+_+") (pintype "passive"))
      (node (ref "PS1_5V") (pin "1") (pinfunction "+VIN_1") (pintype "input"))
      (node (ref "PS2_3.3V") (pin "1") (pinfunction "+VIN_1") (pintype "input"))
    )
    (net (code "85") (name "Net-(PS3_12V-+VIN)") (class "Default")
      (node (ref "B5") (pin "+") (pinfunction "+_+") (pintype "passive"))
      (node (ref "C2_10UF") (pin "+") (pinfunction "+_+") (pintype "passive"))
      (node (ref "PS3_12V") (pin "1") (pinfunction "+VIN_1") (pintype "input"))
    )
    (net (code "86") (name "Net-(PS4_12V-+VIN)") (class "Default")
      (node (ref "B1") (pin "+") (pinfunction "+_+") (pintype "passive"))
      (node (ref "C7") (pin "+") (pinfunction "+_+") (pintype "passive"))
      (node (ref "PS4_12V") (pin "1") (pinfunction "+VIN_1") (pintype "input"))
    )
    (net (code "87") (name "Net-(PS5_5V-+VIN)") (class "Default")
      (node (ref "B2") (pin "+") (pinfunction "+_+") (pintype "passive"))
      (node (ref "C3") (pin "+") (pinfunction "+_+") (pintype "passive"))
      (node (ref "PS5_5V") (pin "1") (pinfunction "+VIN_1") (pintype "input"))
      (node (ref "PS6_15V") (pin "1") (pinfunction "+VIN_1") (pintype "input"))
    )
    (net (code "88") (name "Net-(R14-Pad1)") (class "Default")
      (node (ref "R14") (pin "1") (pinfunction "1_1") (pintype "passive"))
      (node (ref "T1") (pin "C") (pinfunction "C_C") (pintype "passive"))
    )
    (net (code "89") (name "Net-(U$1-15V1)") (class "Default")
      (node (ref "B2") (pin "AC2") (pinfunction "AC2_AC2") (pintype "passive"))
      (node (ref "U$1") (pin "P$11") (pinfunction "15V1_P$11") (pintype "bidirectional"))
    )
    (net (code "90") (name "Net-(U$1-15V2)") (class "Default")
      (node (ref "B2") (pin "AC1") (pinfunction "AC1_AC1") (pintype "passive"))
      (node (ref "U$1") (pin "P$12") (pinfunction "15V2_P$12") (pintype "bidirectional"))
    )
    (net (code "91") (name "Net-(U$5-VREF)") (class "Default")
      (node (ref "U$5") (pin "12") (pinfunction "VREF_12") (pintype "bidirectional"))
      (node (ref "X9") (pin "1") (pinfunction "S_1") (pintype "passive"))
    )
    (net (code "92") (name "Net-(U$7-VREF)") (class "Default")
      (node (ref "U$7") (pin "12") (pinfunction "VREF_12") (pintype "bidirectional"))
      (node (ref "X10") (pin "1") (pinfunction "S_1") (pintype "passive"))
    )
    (net (code "93") (name "Net-(U$12-VIN+)") (class "Default")
      (node (ref "C59") (pin "1") (pinfunction "1_1") (pintype "passive"))
      (node (ref "R37") (pin "1") (pinfunction "1_1") (pintype "passive"))
      (node (ref "R38") (pin "2") (pinfunction "2_2") (pintype "passive"))
      (node (ref "U$12") (pin "2") (pinfunction "VIN+_2") (pintype "bidirectional"))
    )
    (net (code "94") (name "Net-(U$16-AC-IN1)") (class "Default")
      (node (ref "U$11") (pin "2") (pinfunction "2_2") (pintype "bidirectional"))
      (node (ref "U$16") (pin "P$3") (pinfunction "AC-IN1_P$3") (pintype "bidirectional"))
      (node (ref "U$9") (pin "1") (pinfunction "1_1") (pintype "bidirectional"))
      (node (ref "X6") (pin "1") (pinfunction "1_1") (pintype "passive"))
    )
    (net (code "95") (name "Net-(U$16-AC-IN2)") (class "Default")
      (node (ref "U$10") (pin "2") (pinfunction "2_2") (pintype "bidirectional"))
      (node (ref "U$16") (pin "P$4") (pinfunction "AC-IN2_P$4") (pintype "bidirectional"))
      (node (ref "U$9") (pin "2") (pinfunction "2_2") (pintype "bidirectional"))
      (node (ref "X6") (pin "2") (pinfunction "1_2") (pintype "passive"))
    )
    (net (code "96") (name "Net-(U$16-AC-IN3)") (class "Default")
      (node (ref "U$10") (pin "1") (pinfunction "1_1") (pintype "bidirectional"))
      (node (ref "U$11") (pin "1") (pinfunction "1_1") (pintype "bidirectional"))
      (node (ref "U$16") (pin "P$5") (pinfunction "AC-IN3_P$5") (pintype "bidirectional"))
      (node (ref "X6") (pin "3") (pinfunction "1_3") (pintype "passive"))
    )
    (net (code "97") (name "Net-(U2-REFCAPA)") (class "Default")
      (node (ref "C41") (pin "1") (pinfunction "1_1") (pintype "passive"))
      (node (ref "U2") (pin "44") (pinfunction "REFCAPA_44") (pintype "output"))
      (node (ref "U2") (pin "45") (pinfunction "REFCAPB_45") (pintype "output"))
    )
    (net (code "98") (name "Net-(U2-REFIN{slash}REFOUT)") (class "Default")
      (node (ref "C42") (pin "2") (pinfunction "2_2") (pintype "passive"))
      (node (ref "U2") (pin "42") (pinfunction "REFIN/REFOUT_42") (pintype "input"))
    )
    (net (code "99") (name "Net-(U2-REGCAP1)") (class "Default")
      (node (ref "C38") (pin "1") (pinfunction "1_1") (pintype "passive"))
      (node (ref "U2") (pin "36") (pinfunction "REGCAP1_36") (pintype "output"))
    )
    (net (code "100") (name "Net-(U2-REGCAP2)") (class "Default")
      (node (ref "C39") (pin "1") (pinfunction "1_1") (pintype "passive"))
      (node (ref "U2") (pin "39") (pinfunction "REGCAP2_39") (pintype "output"))
    )
    (net (code "101") (name "Net-(U16-A)") (class "Default")
      (node (ref "R41") (pin "1") (pinfunction "1_1") (pintype "passive"))
      (node (ref "U16") (pin "1") (pinfunction "A_1") (pintype "passive"))
    )
    (net (code "102") (name "Net-(U21-A)") (class "Default")
      (node (ref "R2") (pin "1") (pinfunction "1_1") (pintype "passive"))
      (node (ref "U21") (pin "1") (pinfunction "A_1") (pintype "passive"))
    )
    (net (code "103") (name "OP_REF_U") (class "Default")
      (node (ref "R12") (pin "1") (pinfunction "1_1") (pintype "passive"))
      (node (ref "R9") (pin "1") (pinfunction "1_1") (pintype "passive"))
      (node (ref "X9") (pin "2") (pinfunction "S_2") (pintype "passive"))
    )
    (net (code "104") (name "OP_REF_W") (class "Default")
      (node (ref "R17") (pin "1") (pinfunction "1_1") (pintype "passive"))
      (node (ref "R23") (pin "1") (pinfunction "1_1") (pintype "passive"))
      (node (ref "X10") (pin "2") (pinfunction "S_2") (pintype "passive"))
    )
    (net (code "105") (name "PG") (class "Default")
      (node (ref "B2") (pin "-") (pinfunction "-_-") (pintype "passive"))
      (node (ref "C3") (pin "-") (pinfunction "-_-") (pintype "passive"))
      (node (ref "C36") (pin "2") (pinfunction "2_2") (pintype "passive"))
      (node (ref "C36_100NF") (pin "2") (pinfunction "2_2") (pintype "passive"))
      (node (ref "C37") (pin "-") (pinfunction "-_-") (pintype "passive"))
      (node (ref "C37_10UF") (pin "-") (pinfunction "-_-") (pintype "passive"))
      (node (ref "C45") (pin "2") (pinfunction "2_2") (pintype "passive"))
      (node (ref "C45_10UF") (pin "-") (pinfunction "-_-") (pintype "passive"))
      (node (ref "C50_100NF") (pin "2") (pinfunction "2_2") (pintype "passive"))
      (node (ref "C58") (pin "2") (pinfunction "2_2") (pintype "passive"))
      (node (ref "C59") (pin "2") (pinfunction "2_2") (pintype "passive"))
      (node (ref "IC3") (pin "1") (pinfunction "VSS_1") (pintype "bidirectional"))
      (node (ref "PS5_5V") (pin "2") (pinfunction "GND_2") (pintype "power_in"))
      (node (ref "PS6_15V") (pin "2") (pinfunction "GND_2") (pintype "power_in"))
      (node (ref "T2") (pin "E") (pinfunction "E_E") (pintype "passive"))
      (node (ref "TP3") (pin "TP") (pinfunction "TP_TP") (pintype "input"))
      (node (ref "U$12") (pin "3") (pinfunction "VIN-_3") (pintype "bidirectional"))
      (node (ref "U$12") (pin "4") (pinfunction "GND1_4") (pintype "bidirectional"))
      (node (ref "U$2") (pin "2") (pinfunction "2_2") (pintype "passive"))
      (node (ref "U13") (pin "15") (pinfunction "~{GND2}_15") (pintype "passive"))
      (node (ref "U13") (pin "9") (pinfunction "~{GND2}_9") (pintype "passive"))
      (node (ref "U16") (pin "3") (pinfunction "ET_3") (pintype "passive"))
      (node (ref "U17") (pin "15") (pinfunction "~{GND2}_15") (pintype "passive"))
      (node (ref "U17") (pin "9") (pinfunction "~{GND2}_9") (pintype "passive"))
      (node (ref "U22") (pin "3") (pinfunction "ET_3") (pintype "passive"))
    )
    (net (code "106") (name "PWM_U_H_LG") (class "Default")
      (node (ref "TP11") (pin "TP") (pinfunction "TP_TP") (pintype "input"))
      (node (ref "U17") (pin "3") (pinfunction "VIA_3") (pintype "passive"))
      (node (ref "U18") (pin "3") (pinfunction "OUT_3") (pintype "output"))
    )
    (net (code "107") (name "PWM_U_H_LG_DIFF_A") (class "Default")
      (node (ref "U18") (pin "2") (pinfunction "A_2") (pintype "input"))
      (node (ref "X4") (pin "28") (pinfunction "KL_28") (pintype "passive"))
    )
    (net (code "108") (name "PWM_U_H_LG_DIFF_B") (class "Default")
      (node (ref "U18") (pin "1") (pinfunction "B_1") (pintype "input"))
      (node (ref "X4") (pin "26") (pinfunction "KL_26") (pintype "passive"))
    )
    (net (code "109") (name "PWM_U_H_PG") (class "Default")
      (node (ref "IC3") (pin "3") (pinfunction "HIN(U)_3") (pintype "bidirectional"))
      (node (ref "TP5") (pin "TP") (pinfunction "TP_TP") (pintype "input"))
      (node (ref "U17") (pin "14") (pinfunction "VOA_14") (pintype "passive"))
    )
    (net (code "110") (name "PWM_U_L_LG") (class "Default")
      (node (ref "TP8") (pin "TP") (pinfunction "TP_TP") (pintype "input"))
      (node (ref "U13") (pin "3") (pinfunction "VIA_3") (pintype "passive"))
      (node (ref "U19") (pin "3") (pinfunction "OUT_3") (pintype "output"))
    )
    (net (code "111") (name "PWM_U_L_LG_DIFF_A") (class "Default")
      (node (ref "U19") (pin "2") (pinfunction "A_2") (pintype "input"))
      (node (ref "X4") (pin "2") (pinfunction "KL_2") (pintype "passive"))
    )
    (net (code "112") (name "PWM_U_L_LG_DIFF_B") (class "Default")
      (node (ref "U19") (pin "1") (pinfunction "B_1") (pintype "input"))
      (node (ref "X4") (pin "4") (pinfunction "KL_4") (pintype "passive"))
    )
    (net (code "113") (name "PWM_U_L_PG") (class "Default")
      (node (ref "IC3") (pin "6") (pinfunction "LIN(U)_6") (pintype "bidirectional"))
      (node (ref "PWM_U_L_PG") (pin "TP") (pinfunction "TP_TP") (pintype "input"))
      (node (ref "U13") (pin "14") (pinfunction "VOA_14") (pintype "passive"))
    )
    (net (code "114") (name "PWM_V_H_LG") (class "Default")
      (node (ref "TP12") (pin "TP") (pinfunction "TP_TP") (pintype "input"))
      (node (ref "U17") (pin "4") (pinfunction "VIB_4") (pintype "passive"))
      (node (ref "U18") (pin "13") (pinfunction "OUT_13") (pintype "output"))
    )
    (net (code "115") (name "PWM_V_H_LG_DIFF_A") (class "Default")
      (node (ref "U18") (pin "14") (pinfunction "A_14") (pintype "input"))
      (node (ref "X4") (pin "18") (pinfunction "KL_18") (pintype "passive"))
    )
    (net (code "116") (name "PWM_V_H_LG_DIFF_B") (class "Default")
      (node (ref "U18") (pin "15") (pinfunction "B_15") (pintype "input"))
      (node (ref "X4") (pin "20") (pinfunction "KL_20") (pintype "passive"))
    )
    (net (code "117") (name "PWM_V_H_PG") (class "Default")
      (node (ref "IC3") (pin "4") (pinfunction "HIN(V)_4") (pintype "bidirectional"))
      (node (ref "TP6") (pin "TP") (pinfunction "TP_TP") (pintype "input"))
      (node (ref "U17") (pin "13") (pinfunction "VOB_13") (pintype "passive"))
    )
    (net (code "118") (name "PWM_V_L_LG") (class "Default")
      (node (ref "TP9") (pin "TP") (pinfunction "TP_TP") (pintype "input"))
      (node (ref "U13") (pin "4") (pinfunction "VIB_4") (pintype "passive"))
      (node (ref "U19") (pin "13") (pinfunction "OUT_13") (pintype "output"))
    )
    (net (code "119") (name "PWM_V_L_LG_DIFF_A") (class "Default")
      (node (ref "U19") (pin "14") (pinfunction "A_14") (pintype "input"))
      (node (ref "X4") (pin "10") (pinfunction "KL_10") (pintype "passive"))
    )
    (net (code "120") (name "PWM_V_L_LG_DIFF_B") (class "Default")
      (node (ref "U19") (pin "15") (pinfunction "B_15") (pintype "input"))
      (node (ref "X4") (pin "12") (pinfunction "KL_12") (pintype "passive"))
    )
    (net (code "121") (name "PWM_V_L_PG") (class "Default")
      (node (ref "IC3") (pin "7") (pinfunction "LIN(V)_7") (pintype "bidirectional"))
      (node (ref "PWM_V_L_PG") (pin "TP") (pinfunction "TP_TP") (pintype "input"))
      (node (ref "U13") (pin "13") (pinfunction "VOB_13") (pintype "passive"))
    )
    (net (code "122") (name "PWM_W_H_LG") (class "Default")
      (node (ref "TP13") (pin "TP") (pinfunction "TP_TP") (pintype "input"))
      (node (ref "U17") (pin "5") (pinfunction "VIC_5") (pintype "passive"))
      (node (ref "U18") (pin "5") (pinfunction "OUT_5") (pintype "output"))
    )
    (net (code "123") (name "PWM_W_H_LG_DIFF_A") (class "Default")
      (node (ref "U18") (pin "6") (pinfunction "A_6") (pintype "input"))
      (node (ref "X4") (pin "24") (pinfunction "KL_24") (pintype "passive"))
    )
    (net (code "124") (name "PWM_W_H_LG_DIFF_B") (class "Default")
      (node (ref "U18") (pin "7") (pinfunction "B_7") (pintype "input"))
      (node (ref "X4") (pin "22") (pinfunction "KL_22") (pintype "passive"))
    )
    (net (code "125") (name "PWM_W_H_PG") (class "Default")
      (node (ref "IC3") (pin "5") (pinfunction "HIN(W)_5") (pintype "bidirectional"))
      (node (ref "TP7") (pin "TP") (pinfunction "TP_TP") (pintype "input"))
      (node (ref "U17") (pin "12") (pinfunction "VOC_12") (pintype "passive"))
    )
    (net (code "126") (name "PWM_W_L_LG") (class "Default")
      (node (ref "TP10") (pin "TP") (pinfunction "TP_TP") (pintype "input"))
      (node (ref "U13") (pin "5") (pinfunction "VIC_5") (pintype "passive"))
      (node (ref "U19") (pin "5") (pinfunction "OUT_5") (pintype "output"))
    )
    (net (code "127") (name "PWM_W_L_LG_DIFF_A") (class "Default")
      (node (ref "U19") (pin "6") (pinfunction "A_6") (pintype "input"))
      (node (ref "X4") (pin "6") (pinfunction "KL_6") (pintype "passive"))
    )
    (net (code "128") (name "PWM_W_L_LG_DIFF_B") (class "Default")
      (node (ref "U19") (pin "7") (pinfunction "B_7") (pintype "input"))
      (node (ref "X4") (pin "8") (pinfunction "KL_8") (pintype "passive"))
    )
    (net (code "129") (name "PWM_W_L_PG") (class "Default")
      (node (ref "IC3") (pin "8") (pinfunction "LIN(W)_8") (pintype "bidirectional"))
      (node (ref "TP4") (pin "TP") (pinfunction "TP_TP") (pintype "input"))
      (node (ref "U13") (pin "12") (pinfunction "VOC_12") (pintype "passive"))
    )
    (net (code "130") (name "SOFT_RELAY_LG") (class "Default")
      (node (ref "U14") (pin "11") (pinfunction "OUT_11") (pintype "output"))
      (node (ref "U16") (pin "2") (pinfunction "C_2") (pintype "passive"))
    )
    (net (code "131") (name "SOFT_RELAY_LG_DIFF_A") (class "Default")
      (node (ref "U14") (pin "10") (pinfunction "A_10") (pintype "input"))
      (node (ref "X4") (pin "39") (pinfunction "KL_39") (pintype "passive"))
    )
    (net (code "132") (name "SOFT_RELAY_LG_DIFF_B") (class "Default")
      (node (ref "U14") (pin "9") (pinfunction "B_9") (pintype "input"))
      (node (ref "X4") (pin "37") (pinfunction "KL_37") (pintype "passive"))
    )
    (net (code "133") (name "SOFT_RELAY_PG") (class "Default")
      (node (ref "R42") (pin "1") (pinfunction "1_1") (pintype "passive"))
      (node (ref "T2") (pin "B") (pinfunction "B_B") (pintype "passive"))
      (node (ref "U16") (pin "4") (pinfunction "CT_4") (pintype "passive"))
    )
    (net (code "134") (name "U") (class "Default")
      (node (ref "U$5") (pin "6") (pinfunction "IN6_6") (pintype "bidirectional"))
      (node (ref "U$5") (pin "7") (pinfunction "IN7_7") (pintype "bidirectional"))
      (node (ref "U$5") (pin "8") (pinfunction "IN8_8") (pintype "bidirectional"))
      (node (ref "U$5") (pin "9") (pinfunction "IN9_9") (pintype "bidirectional"))
      (node (ref "X3") (pin "1") (pinfunction "1_1") (pintype "passive"))
    )
    (net (code "135") (name "V") (class "Default")
      (node (ref "C46") (pin "-") (pinfunction "-_-") (pintype "passive"))
      (node (ref "C47") (pin "2") (pinfunction "2_2") (pintype "passive"))
      (node (ref "IC3") (pin "26") (pinfunction "VS(V),_V_26") (pintype "bidirectional"))
      (node (ref "X3") (pin "2") (pinfunction "1_2") (pintype "passive"))
    )
    (net (code "136") (name "VBUS_ADC") (class "Default")
      (node (ref "IC1") (pin "1") (pinfunction "OUT_1") (pintype "output"))
      (node (ref "R3") (pin "2") (pinfunction "2_2") (pintype "passive"))
      (node (ref "U2") (pin "59") (pinfunction "AIN_4P_59") (pintype "input"))
    )
    (net (code "137") (name "VO_HCPL") (class "Default")
      (node (ref "C60") (pin "1") (pinfunction "1_1") (pintype "bidirectional"))
      (node (ref "R7") (pin "1") (pinfunction "1_1") (pintype "passive"))
      (node (ref "U$12") (pin "7") (pinfunction "VOUT_7") (pintype "bidirectional"))
    )
    (net (code "138") (name "W") (class "Default")
      (node (ref "U$7") (pin "6") (pinfunction "IN6_6") (pintype "bidirectional"))
      (node (ref "U$7") (pin "7") (pinfunction "IN7_7") (pintype "bidirectional"))
      (node (ref "U$7") (pin "8") (pinfunction "IN8_8") (pintype "bidirectional"))
      (node (ref "U$7") (pin "9") (pinfunction "IN9_9") (pintype "bidirectional"))
      (node (ref "X3") (pin "3") (pinfunction "1_3") (pintype "passive"))
    )
    (net (code "139") (name "unconnected-(IC2-PadR)") (class "Default")
      (node (ref "IC2") (pin "R") (pinfunction "R_R") (pintype "passive"))
    )
    (net (code "140") (name "unconnected-(IC3-TH1-Pad13)") (class "Default")
      (node (ref "IC3") (pin "13") (pinfunction "TH1_13") (pintype "bidirectional"))
    )
    (net (code "141") (name "unconnected-(IC3-TH2-Pad14)") (class "Default")
      (node (ref "IC3") (pin "14") (pinfunction "TH2_14") (pintype "bidirectional"))
    )
    (net (code "142") (name "unconnected-(IC6-PadR)") (class "Default")
      (node (ref "IC6") (pin "R") (pinfunction "R_R") (pintype "passive"))
    )
    (net (code "143") (name "unconnected-(IC7-PadR)") (class "Default")
      (node (ref "IC7") (pin "R") (pinfunction "R_R") (pintype "passive"))
    )
    (net (code "144") (name "unconnected-(R1-Pad1)") (class "Default")
      (node (ref "R1") (pin "1") (pinfunction "1_1") (pintype "passive"))
    )
    (net (code "145") (name "unconnected-(R1-Pad2)") (class "Default")
      (node (ref "R1") (pin "2") (pinfunction "2_2") (pintype "passive"))
    )
    (net (code "146") (name "unconnected-(U$5-OCD-Pad11)") (class "Default")
      (node (ref "U$5") (pin "11") (pinfunction "OCD_11") (pintype "bidirectional"))
    )
    (net (code "147") (name "unconnected-(U$7-OCD-Pad11)") (class "Default")
      (node (ref "U$7") (pin "11") (pinfunction "OCD_11") (pintype "bidirectional"))
    )
    (net (code "148") (name "unconnected-(U2-AIN_2P-Pad51)") (class "Default")
      (node (ref "U2") (pin "51") (pinfunction "AIN_2P_51") (pintype "input"))
    )
    (net (code "149") (name "unconnected-(U2-DB0-Pad16)") (class "Default")
      (node (ref "U2") (pin "16") (pinfunction "DB0_16") (pintype "output"))
    )
    (net (code "150") (name "unconnected-(U2-DB1-Pad17)") (class "Default")
      (node (ref "U2") (pin "17") (pinfunction "DB1_17") (pintype "output"))
    )
    (net (code "151") (name "unconnected-(U2-DB2-Pad18)") (class "Default")
      (node (ref "U2") (pin "18") (pinfunction "DB2_18") (pintype "output"))
    )
    (net (code "152") (name "unconnected-(U2-DB3-Pad19)") (class "Default")
      (node (ref "U2") (pin "19") (pinfunction "DB3_19") (pintype "output"))
    )
    (net (code "153") (name "unconnected-(U2-DB4-Pad20)") (class "Default")
      (node (ref "U2") (pin "20") (pinfunction "DB4_20") (pintype "output"))
    )
    (net (code "154") (name "unconnected-(U2-DB5-Pad21)") (class "Default")
      (node (ref "U2") (pin "21") (pinfunction "DB5_21") (pintype "output"))
    )
    (net (code "155") (name "unconnected-(U2-DB6-Pad22)") (class "Default")
      (node (ref "U2") (pin "22") (pinfunction "DB6_22") (pintype "output"))
    )
    (net (code "156") (name "unconnected-(U2-DB9-Pad27)") (class "Default")
      (node (ref "U2") (pin "27") (pinfunction "DB9_27") (pintype "output"))
    )
    (net (code "157") (name "unconnected-(U2-DB10-Pad28)") (class "Default")
      (node (ref "U2") (pin "28") (pinfunction "DB10_28") (pintype "output"))
    )
    (net (code "158") (name "unconnected-(U2-DB11-Pad29)") (class "Default")
      (node (ref "U2") (pin "29") (pinfunction "DB11_29") (pintype "output"))
    )
    (net (code "159") (name "unconnected-(U2-DB12-Pad30)") (class "Default")
      (node (ref "U2") (pin "30") (pinfunction "DB12_30") (pintype "output"))
    )
    (net (code "160") (name "unconnected-(U2-DB13-Pad31)") (class "Default")
      (node (ref "U2") (pin "31") (pinfunction "DB13_31") (pintype "output"))
    )
    (net (code "161") (name "unconnected-(U2-FRSTDATA-Pad15)") (class "Default")
      (node (ref "U2") (pin "15") (pinfunction "FRSTDATA_15") (pintype "output"))
    )
    (net (code "162") (name "unconnected-(U2-OS0-Pad3)") (class "Default")
      (node (ref "U2") (pin "3") (pinfunction "OS0_3") (pintype "input"))
    )
    (net (code "163") (name "unconnected-(U2-OS1-Pad4)") (class "Default")
      (node (ref "U2") (pin "4") (pinfunction "OS1_4") (pintype "input"))
    )
    (net (code "164") (name "unconnected-(U2-OS2-Pad5)") (class "Default")
      (node (ref "U2") (pin "5") (pinfunction "OS2_5") (pintype "input"))
    )
    (net (code "165") (name "unconnected-(U6-V+-Pad11)") (class "Default")
      (node (ref "U6") (pin "11") (pinfunction "V+_11") (pintype "power_in"))
    )
    (net (code "166") (name "unconnected-(U6-V--Pad6)") (class "Default")
      (node (ref "U6") (pin "6") (pinfunction "V-_6") (pintype "power_in"))
    )
    (net (code "167") (name "unconnected-(U13-CTRL2-Pad10)") (class "Default")
      (node (ref "U13") (pin "10") (pinfunction "CTRL2_10") (pintype "passive"))
    )
    (net (code "168") (name "unconnected-(U13-DISABLE-Pad7)") (class "Default")
      (node (ref "U13") (pin "7") (pinfunction "DISABLE_7") (pintype "passive"))
    )
    (net (code "169") (name "unconnected-(U13-NC-Pad11)") (class "Default")
      (node (ref "U13") (pin "11") (pinfunction "NC_11") (pintype "no_connect"))
    )
    (net (code "170") (name "unconnected-(U13-NC_2-Pad6)") (class "Default")
      (node (ref "U13") (pin "6") (pinfunction "NC_2_6") (pintype "no_connect"))
    )
    (net (code "171") (name "unconnected-(U17-CTRL2-Pad10)") (class "Default")
      (node (ref "U17") (pin "10") (pinfunction "CTRL2_10") (pintype "passive"))
    )
    (net (code "172") (name "unconnected-(U17-DISABLE-Pad7)") (class "Default")
      (node (ref "U17") (pin "7") (pinfunction "DISABLE_7") (pintype "passive"))
    )
    (net (code "173") (name "unconnected-(U17-NC-Pad11)") (class "Default")
      (node (ref "U17") (pin "11") (pinfunction "NC_11") (pintype "no_connect"))
    )
    (net (code "174") (name "unconnected-(U17-NC_2-Pad6)") (class "Default")
      (node (ref "U17") (pin "6") (pinfunction "NC_2_6") (pintype "no_connect"))
    )
    (net (code "175") (name "unconnected-(X2A-KL-Pad1)") (class "Default")
      (node (ref "X2") (pin "1") (pinfunction "KL_1") (pintype "passive"))
    )
    (net (code "176") (name "unconnected-(X4AD-KL-Pad36)") (class "Default")
      (node (ref "X4") (pin "36") (pinfunction "KL_36") (pintype "passive"))
    )
    (net (code "177") (name "unconnected-(X4AF-KL-Pad38)") (class "Default")
      (node (ref "X4") (pin "38") (pinfunction "KL_38") (pintype "passive"))
    )
    (net (code "178") (name "unconnected-(X4AI-KL-Pad40)") (class "Default")
      (node (ref "X4") (pin "40") (pinfunction "KL_40") (pintype "passive"))
    )
  )
)
